# FPGA_DENDY_SE.net
KiCad netlist of a schematic drawn in EAGLE
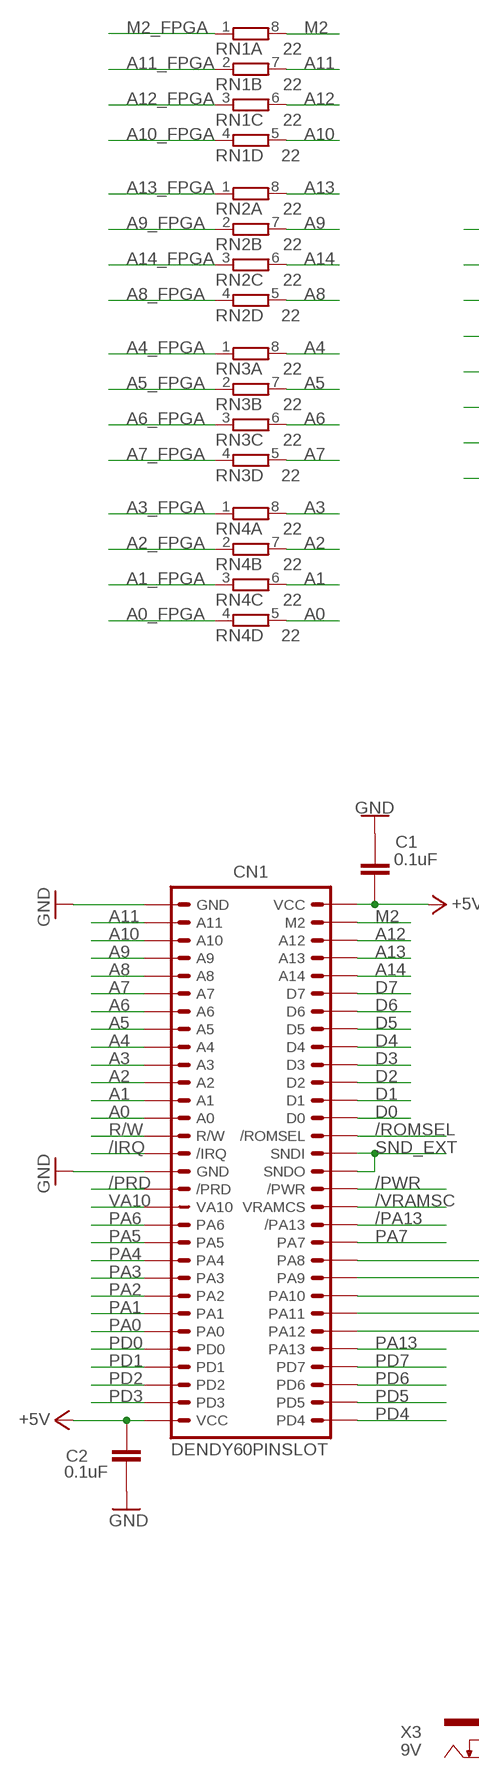
[diagram p0: schematic, sheet 1, part 1 of 2]
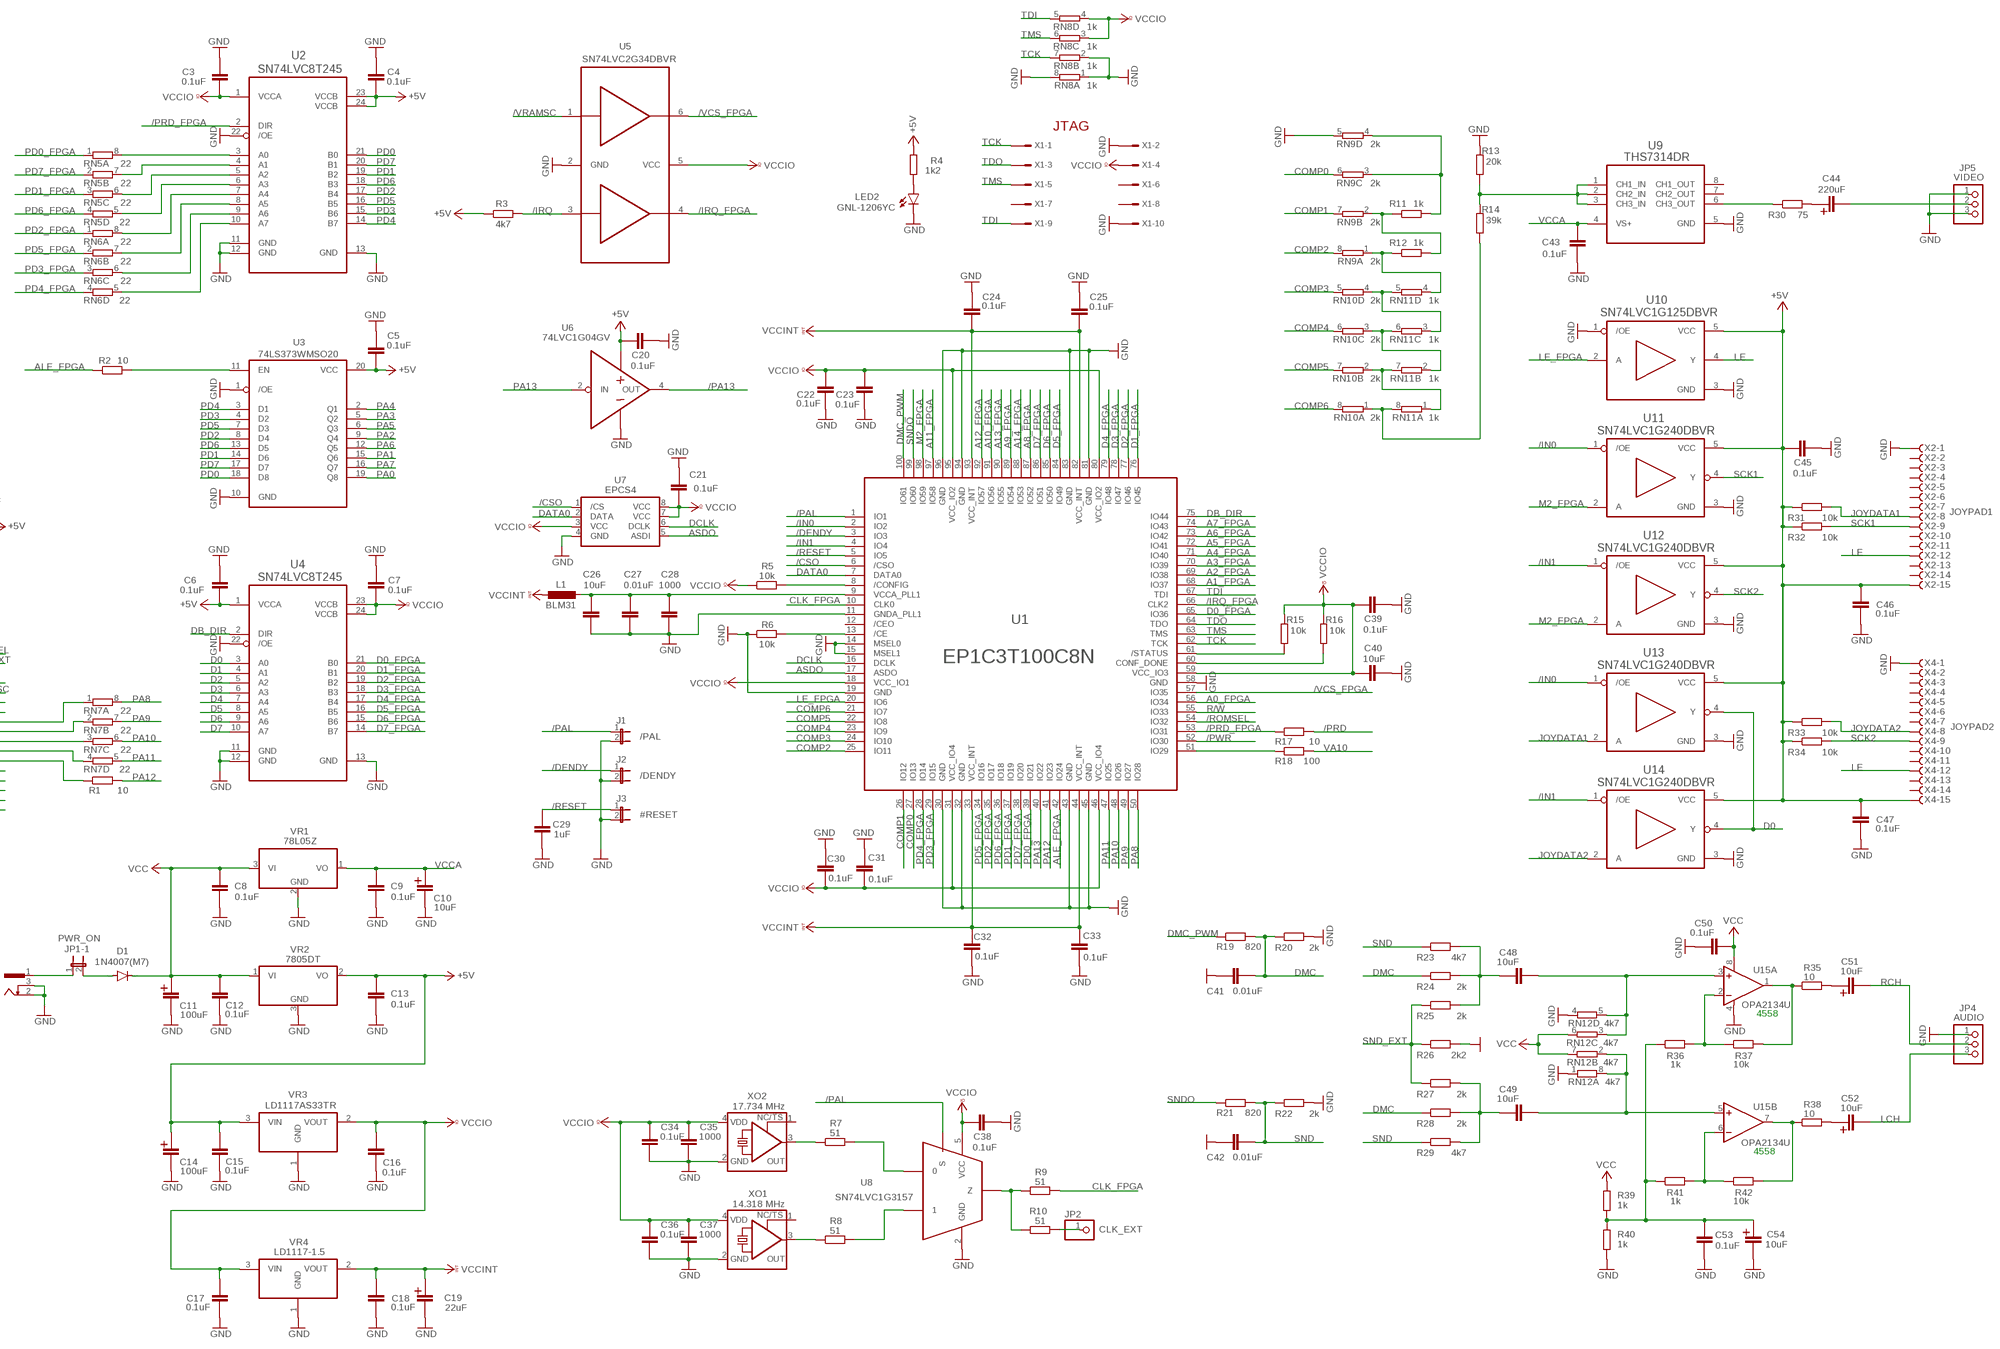
[diagram p1: schematic, sheet 1, part 2 of 2]

(export (version "E")
  (design (tool "Eeschema 10.0.6"))
  (components
    (comp (ref "C1")
      (value "0.1uF")
      (footprint "eagle-import:C0805")
      (libsource (lib "eagle-import") (part "C-EUC0805"))
    )
    (comp (ref "C2")
      (value "0.1uF")
      (footprint "eagle-import:C0805")
      (libsource (lib "eagle-import") (part "C-EUC0805"))
    )
    (comp (ref "C3")
      (value "0.1uF")
      (footprint "eagle-import:C0805")
      (libsource (lib "eagle-import") (part "C-EUC0805"))
    )
    (comp (ref "C4")
      (value "0.1uF")
      (footprint "eagle-import:C0805")
      (libsource (lib "eagle-import") (part "C-EUC0805"))
    )
    (comp (ref "C5")
      (value "0.1uF")
      (footprint "eagle-import:C0805")
      (libsource (lib "eagle-import") (part "C-EUC0805"))
    )
    (comp (ref "C6")
      (value "0.1uF")
      (footprint "eagle-import:C0603")
      (libsource (lib "eagle-import") (part "C-EUC0603"))
    )
    (comp (ref "C7")
      (value "0.1uF")
      (footprint "eagle-import:C0603")
      (libsource (lib "eagle-import") (part "C-EUC0603"))
    )
    (comp (ref "C8")
      (value "0.1uF")
      (footprint "eagle-import:C0805")
      (libsource (lib "eagle-import") (part "C-EUC0805"))
    )
    (comp (ref "C9")
      (value "0.1uF")
      (footprint "eagle-import:C0805")
      (libsource (lib "eagle-import") (part "C-EUC0805"))
    )
    (comp (ref "C10")
      (value "10uF")
      (footprint "eagle-import:153CLV-0505")
      (libsource (lib "eagle-import") (part "CPOL-EU153CLV-0505"))
    )
    (comp (ref "C11")
      (value "100uF")
      (footprint "eagle-import:153CLV-0505")
      (libsource (lib "eagle-import") (part "CPOL-EU153CLV-0505"))
    )
    (comp (ref "C12")
      (value "0.1uF")
      (footprint "eagle-import:C0805")
      (libsource (lib "eagle-import") (part "C-EUC0805"))
    )
    (comp (ref "C13")
      (value "0.1uF")
      (footprint "eagle-import:C0805")
      (libsource (lib "eagle-import") (part "C-EUC0805"))
    )
    (comp (ref "C14")
      (value "100uF")
      (footprint "eagle-import:153CLV-0505")
      (libsource (lib "eagle-import") (part "CPOL-EU153CLV-0505"))
    )
    (comp (ref "C15")
      (value "0.1uF")
      (footprint "eagle-import:C0805")
      (libsource (lib "eagle-import") (part "C-EUC0805"))
    )
    (comp (ref "C16")
      (value "0.1uF")
      (footprint "eagle-import:C0805")
      (libsource (lib "eagle-import") (part "C-EUC0805"))
    )
    (comp (ref "C17")
      (value "0.1uF")
      (footprint "eagle-import:C0805")
      (libsource (lib "eagle-import") (part "C-EUC0805"))
    )
    (comp (ref "C18")
      (value "0.1uF")
      (footprint "eagle-import:C0805")
      (libsource (lib "eagle-import") (part "C-EUC0805"))
    )
    (comp (ref "C19")
      (value "22uF")
      (footprint "eagle-import:153CLV-0505")
      (libsource (lib "eagle-import") (part "CPOL-EU153CLV-0505"))
    )
    (comp (ref "C20")
      (value "0.1uF")
      (footprint "eagle-import:C0603")
      (libsource (lib "eagle-import") (part "C-EUC0603"))
    )
    (comp (ref "C21")
      (value "0.1uF")
      (footprint "eagle-import:C0603")
      (libsource (lib "eagle-import") (part "C-EUC0603"))
    )
    (comp (ref "C22")
      (value "0.1uF")
      (footprint "eagle-import:C0603")
      (libsource (lib "eagle-import") (part "C-EUC0603"))
    )
    (comp (ref "C23")
      (value "0.1uF")
      (footprint "eagle-import:C0603")
      (libsource (lib "eagle-import") (part "C-EUC0603"))
    )
    (comp (ref "C24")
      (value "0.1uF")
      (footprint "eagle-import:C0603")
      (libsource (lib "eagle-import") (part "C-EUC0603"))
    )
    (comp (ref "C25")
      (value "0.1uF")
      (footprint "eagle-import:C0603")
      (libsource (lib "eagle-import") (part "C-EUC0603"))
    )
    (comp (ref "C26")
      (value "10uF")
      (footprint "eagle-import:C0603")
      (libsource (lib "eagle-import") (part "C-EUC0603"))
    )
    (comp (ref "C27")
      (value "0.01uF")
      (footprint "eagle-import:C0603")
      (libsource (lib "eagle-import") (part "C-EUC0603"))
    )
    (comp (ref "C28")
      (value "1000")
      (footprint "eagle-import:C0603")
      (libsource (lib "eagle-import") (part "C-EUC0603"))
    )
    (comp (ref "C29")
      (value "1uF")
      (footprint "eagle-import:C0603")
      (libsource (lib "eagle-import") (part "C-EUC0603"))
    )
    (comp (ref "C30")
      (value "0.1uF")
      (footprint "eagle-import:C0603")
      (libsource (lib "eagle-import") (part "C-EUC0603"))
    )
    (comp (ref "C31")
      (value "0.1uF")
      (footprint "eagle-import:C0603")
      (libsource (lib "eagle-import") (part "C-EUC0603"))
    )
    (comp (ref "C32")
      (value "0.1uF")
      (footprint "eagle-import:C0603")
      (libsource (lib "eagle-import") (part "C-EUC0603"))
    )
    (comp (ref "C33")
      (value "0.1uF")
      (footprint "eagle-import:C0603")
      (libsource (lib "eagle-import") (part "C-EUC0603"))
    )
    (comp (ref "C34")
      (value "0.1uF")
      (footprint "eagle-import:C0805")
      (libsource (lib "eagle-import") (part "C-EUC0805"))
    )
    (comp (ref "C35")
      (value "1000")
      (footprint "eagle-import:C0805")
      (libsource (lib "eagle-import") (part "C-EUC0805"))
    )
    (comp (ref "C36")
      (value "0.1uF")
      (footprint "eagle-import:C0805")
      (libsource (lib "eagle-import") (part "C-EUC0805"))
    )
    (comp (ref "C37")
      (value "1000")
      (footprint "eagle-import:C0805")
      (libsource (lib "eagle-import") (part "C-EUC0805"))
    )
    (comp (ref "C38")
      (value "0.1uF")
      (footprint "eagle-import:C0603")
      (libsource (lib "eagle-import") (part "C-EUC0603"))
    )
    (comp (ref "C39")
      (value "0.1uF")
      (footprint "eagle-import:C0603")
      (libsource (lib "eagle-import") (part "C-EUC0603"))
    )
    (comp (ref "C40")
      (value "10uF")
      (footprint "eagle-import:C0603")
      (libsource (lib "eagle-import") (part "C-EUC0603"))
    )
    (comp (ref "C41")
      (value "0.01uF")
      (footprint "eagle-import:C0805")
      (libsource (lib "eagle-import") (part "C-EUC0805"))
    )
    (comp (ref "C42")
      (value "0.01uF")
      (footprint "eagle-import:C0805")
      (libsource (lib "eagle-import") (part "C-EUC0805"))
    )
    (comp (ref "C43")
      (value "0.1uF")
      (footprint "eagle-import:C0603")
      (libsource (lib "eagle-import") (part "C-EUC0603"))
    )
    (comp (ref "C44")
      (value "220uF")
      (footprint "eagle-import:153CLV-0505")
      (libsource (lib "eagle-import") (part "CPOL-EU153CLV-0505"))
    )
    (comp (ref "C45")
      (value "0.1uF")
      (footprint "eagle-import:C0603")
      (libsource (lib "eagle-import") (part "C-EUC0603"))
    )
    (comp (ref "C46")
      (value "0.1uF")
      (footprint "eagle-import:C0805")
      (libsource (lib "eagle-import") (part "C-EUC0805"))
    )
    (comp (ref "C47")
      (value "0.1uF")
      (footprint "eagle-import:C0805")
      (libsource (lib "eagle-import") (part "C-EUC0805"))
    )
    (comp (ref "C48")
      (value "10uF")
      (footprint "eagle-import:C0805")
      (libsource (lib "eagle-import") (part "C-EUC0805"))
    )
    (comp (ref "C49")
      (value "10uF")
      (footprint "eagle-import:C0805")
      (libsource (lib "eagle-import") (part "C-EUC0805"))
    )
    (comp (ref "C50")
      (value "0.1uF")
      (footprint "eagle-import:C0805")
      (libsource (lib "eagle-import") (part "C-EUC0805"))
    )
    (comp (ref "C51")
      (value "10uF")
      (footprint "eagle-import:153CLV-0505")
      (libsource (lib "eagle-import") (part "CPOL-EU153CLV-0505"))
    )
    (comp (ref "C52")
      (value "10uF")
      (footprint "eagle-import:153CLV-0505")
      (libsource (lib "eagle-import") (part "CPOL-EU153CLV-0505"))
    )
    (comp (ref "C53")
      (value "0.1uF")
      (footprint "eagle-import:C0805")
      (libsource (lib "eagle-import") (part "C-EUC0805"))
    )
    (comp (ref "C54")
      (value "10uF")
      (footprint "eagle-import:153CLV-0505")
      (libsource (lib "eagle-import") (part "CPOL-EU153CLV-0505"))
    )
    (comp (ref "CN1")
      (value "DENDY60PINSLOT")
      (footprint "eagle-import:60PINDENDY")
      (libsource (lib "eagle-import") (part "DENDY60PINSLOT"))
    )
    (comp (ref "D1")
      (value "1N4007(M7)")
      (footprint "eagle-import:DO-214AC")
      (libsource (lib "eagle-import") (part "DIODE-DO-214AC"))
    )
    (comp (ref "J1")
      (value "/PAL")
      (footprint "eagle-import:JP1")
      (libsource (lib "eagle-import") (part "JP1E"))
    )
    (comp (ref "J2")
      (value "/DENDY")
      (footprint "eagle-import:JP1")
      (libsource (lib "eagle-import") (part "JP1E"))
    )
    (comp (ref "J3")
      (value "#RESET")
      (footprint "eagle-import:JP1")
      (libsource (lib "eagle-import") (part "JP1E"))
    )
    (comp (ref "JP1")
      (value "PWR_ON")
      (footprint "eagle-import:JP4Q")
      (libsource (lib "eagle-import") (part "JP4QE"))
    )
    (comp (ref "JP2")
      (value "CLK_EXT")
      (footprint "eagle-import:1X01")
      (libsource (lib "eagle-import") (part "PINHD-1X1"))
    )
    (comp (ref "JP4")
      (value "AUDIO")
      (footprint "eagle-import:1X03")
      (libsource (lib "eagle-import") (part "PINHD-1X3"))
    )
    (comp (ref "JP5")
      (value "VIDEO")
      (footprint "eagle-import:1X03")
      (libsource (lib "eagle-import") (part "PINHD-1X3"))
    )
    (comp (ref "L1")
      (value "BLM31")
      (footprint "eagle-import:L0201")
      (libsource (lib "eagle-import") (part "L-EUL0201"))
    )
    (comp (ref "LED2")
      (value "GNL-1206YC")
      (footprint "eagle-import:SML1206")
      (libsource (lib "eagle-import") (part "LEDSML1206"))
    )
    (comp (ref "R1")
      (value "10")
      (footprint "eagle-import:R0805")
      (libsource (lib "eagle-import") (part "R-EU_R0805"))
    )
    (comp (ref "R2")
      (value "10")
      (footprint "eagle-import:R0805")
      (libsource (lib "eagle-import") (part "R-EU_R0805"))
    )
    (comp (ref "R3")
      (value "4k7")
      (footprint "eagle-import:R0805")
      (libsource (lib "eagle-import") (part "R-EU_R0805"))
    )
    (comp (ref "R4")
      (value "1k2")
      (footprint "eagle-import:R0805")
      (libsource (lib "eagle-import") (part "R-EU_R0805"))
    )
    (comp (ref "R5")
      (value "10k")
      (footprint "eagle-import:R0805")
      (libsource (lib "eagle-import") (part "R-EU_R0805"))
    )
    (comp (ref "R6")
      (value "10k")
      (footprint "eagle-import:R0805")
      (libsource (lib "eagle-import") (part "R-EU_R0805"))
    )
    (comp (ref "R7")
      (value "51")
      (footprint "eagle-import:R0805")
      (libsource (lib "eagle-import") (part "R-EU_R0805"))
    )
    (comp (ref "R8")
      (value "51")
      (footprint "eagle-import:R0805")
      (libsource (lib "eagle-import") (part "R-EU_R0805"))
    )
    (comp (ref "R9")
      (value "51")
      (footprint "eagle-import:R0805")
      (libsource (lib "eagle-import") (part "R-EU_R0805"))
    )
    (comp (ref "R10")
      (value "51")
      (footprint "eagle-import:R0805")
      (libsource (lib "eagle-import") (part "R-EU_R0805"))
    )
    (comp (ref "R11")
      (value "1k")
      (footprint "eagle-import:R0805")
      (libsource (lib "eagle-import") (part "R-EU_R0805"))
    )
    (comp (ref "R12")
      (value "1k")
      (footprint "eagle-import:R0805")
      (libsource (lib "eagle-import") (part "R-EU_R0805"))
    )
    (comp (ref "R13")
      (value "20k")
      (footprint "eagle-import:R0805")
      (libsource (lib "eagle-import") (part "R-EU_R0805"))
    )
    (comp (ref "R14")
      (value "39k")
      (footprint "eagle-import:R0805")
      (libsource (lib "eagle-import") (part "R-EU_R0805"))
    )
    (comp (ref "R15")
      (value "10k")
      (footprint "eagle-import:R0805")
      (libsource (lib "eagle-import") (part "R-EU_R0805"))
    )
    (comp (ref "R16")
      (value "10k")
      (footprint "eagle-import:R0805")
      (libsource (lib "eagle-import") (part "R-EU_R0805"))
    )
    (comp (ref "R17")
      (value "10")
      (footprint "eagle-import:R0805")
      (libsource (lib "eagle-import") (part "R-EU_R0805"))
    )
    (comp (ref "R18")
      (value "100")
      (footprint "eagle-import:R0805")
      (libsource (lib "eagle-import") (part "R-EU_R0805"))
    )
    (comp (ref "R19")
      (value "820")
      (footprint "eagle-import:R0805")
      (libsource (lib "eagle-import") (part "R-EU_R0805"))
    )
    (comp (ref "R20")
      (value "2k")
      (footprint "eagle-import:R0805")
      (libsource (lib "eagle-import") (part "R-EU_R0805"))
    )
    (comp (ref "R21")
      (value "820")
      (footprint "eagle-import:R0805")
      (libsource (lib "eagle-import") (part "R-EU_R0805"))
    )
    (comp (ref "R22")
      (value "2k")
      (footprint "eagle-import:R0805")
      (libsource (lib "eagle-import") (part "R-EU_R0805"))
    )
    (comp (ref "R23")
      (value "4k7")
      (footprint "eagle-import:R0805")
      (libsource (lib "eagle-import") (part "R-EU_R0805"))
    )
    (comp (ref "R24")
      (value "2k")
      (footprint "eagle-import:R0805")
      (libsource (lib "eagle-import") (part "R-EU_R0805"))
    )
    (comp (ref "R25")
      (value "2k")
      (footprint "eagle-import:R0805")
      (libsource (lib "eagle-import") (part "R-EU_R0805"))
    )
    (comp (ref "R26")
      (value "2k2")
      (footprint "eagle-import:R0805")
      (libsource (lib "eagle-import") (part "R-EU_R0805"))
    )
    (comp (ref "R27")
      (value "2k")
      (footprint "eagle-import:R0805")
      (libsource (lib "eagle-import") (part "R-EU_R0805"))
    )
    (comp (ref "R28")
      (value "2k")
      (footprint "eagle-import:R0805")
      (libsource (lib "eagle-import") (part "R-EU_R0805"))
    )
    (comp (ref "R29")
      (value "4k7")
      (footprint "eagle-import:R0805")
      (libsource (lib "eagle-import") (part "R-EU_R0805"))
    )
    (comp (ref "R30")
      (value "75")
      (footprint "eagle-import:R0805")
      (libsource (lib "eagle-import") (part "R-EU_R0805"))
    )
    (comp (ref "R31")
      (value "10k")
      (footprint "eagle-import:R0805")
      (libsource (lib "eagle-import") (part "R-EU_R0805"))
    )
    (comp (ref "R32")
      (value "10k")
      (footprint "eagle-import:R0805")
      (libsource (lib "eagle-import") (part "R-EU_R0805"))
    )
    (comp (ref "R33")
      (value "10k")
      (footprint "eagle-import:R0805")
      (libsource (lib "eagle-import") (part "R-EU_R0805"))
    )
    (comp (ref "R34")
      (value "10k")
      (footprint "eagle-import:R0805")
      (libsource (lib "eagle-import") (part "R-EU_R0805"))
    )
    (comp (ref "R35")
      (value "10")
      (footprint "eagle-import:R0805")
      (libsource (lib "eagle-import") (part "R-EU_R0805"))
    )
    (comp (ref "R36")
      (value "1k")
      (footprint "eagle-import:R0805")
      (libsource (lib "eagle-import") (part "R-EU_R0805"))
    )
    (comp (ref "R37")
      (value "10k")
      (footprint "eagle-import:R0805")
      (libsource (lib "eagle-import") (part "R-EU_R0805"))
    )
    (comp (ref "R38")
      (value "10")
      (footprint "eagle-import:R0805")
      (libsource (lib "eagle-import") (part "R-EU_R0805"))
    )
    (comp (ref "R39")
      (value "1k")
      (footprint "eagle-import:R0805")
      (libsource (lib "eagle-import") (part "R-EU_R0805"))
    )
    (comp (ref "R40")
      (value "1k")
      (footprint "eagle-import:R0805")
      (libsource (lib "eagle-import") (part "R-EU_R0805"))
    )
    (comp (ref "R41")
      (value "1k")
      (footprint "eagle-import:R0805")
      (libsource (lib "eagle-import") (part "R-EU_R0805"))
    )
    (comp (ref "R42")
      (value "10k")
      (footprint "eagle-import:R0805")
      (libsource (lib "eagle-import") (part "R-EU_R0805"))
    )
    (comp (ref "RN1")
      (value "22")
      (footprint "eagle-import:0603-ARC")
      (libsource (lib "eagle-import") (part "4R-N0603-ARC"))
    )
    (comp (ref "RN2")
      (value "22")
      (footprint "eagle-import:0603-ARC")
      (libsource (lib "eagle-import") (part "4R-N0603-ARC"))
    )
    (comp (ref "RN3")
      (value "22")
      (footprint "eagle-import:0603-ARC")
      (libsource (lib "eagle-import") (part "4R-N0603-ARC"))
    )
    (comp (ref "RN4")
      (value "22")
      (footprint "eagle-import:0603-ARC")
      (libsource (lib "eagle-import") (part "4R-N0603-ARC"))
    )
    (comp (ref "RN5")
      (value "22")
      (footprint "eagle-import:0603-ARC")
      (libsource (lib "eagle-import") (part "4R-N0603-ARC"))
    )
    (comp (ref "RN6")
      (value "22")
      (footprint "eagle-import:0603-ARC")
      (libsource (lib "eagle-import") (part "4R-N0603-ARC"))
    )
    (comp (ref "RN7")
      (value "22")
      (footprint "eagle-import:0603-ARC")
      (libsource (lib "eagle-import") (part "4R-N0603-ARC"))
    )
    (comp (ref "RN8")
      (value "1k")
      (footprint "eagle-import:0603-ARC")
      (libsource (lib "eagle-import") (part "4R-N0603-ARC"))
    )
    (comp (ref "RN9")
      (value "2k")
      (footprint "eagle-import:0603-ARC")
      (libsource (lib "eagle-import") (part "4R-N0603-ARC"))
    )
    (comp (ref "RN10")
      (value "2k")
      (footprint "eagle-import:0603-ARC")
      (libsource (lib "eagle-import") (part "4R-N0603-ARC"))
    )
    (comp (ref "RN11")
      (value "1k")
      (footprint "eagle-import:0603-ARC")
      (libsource (lib "eagle-import") (part "4R-N0603-ARC"))
    )
    (comp (ref "RN12")
      (value "4k7")
      (footprint "eagle-import:0603-ARC")
      (libsource (lib "eagle-import") (part "4R-N0603-ARC"))
    )
    (comp (ref "U1")
      (value "EP1C3T100C8N")
      (footprint "eagle-import:QFP50P1600X1600X120-100N")
      (libsource (lib "eagle-import") (part "EP1C3T100C8N"))
    )
    (comp (ref "U2")
      (value "SN74LVC8T245")
      (footprint "eagle-import:SOP65P640X110-24N")
      (libsource (lib "eagle-import") (part "SN74LVC8T245"))
    )
    (comp (ref "U3")
      (value "74LS373WMSO20")
      (footprint "eagle-import:SO20W")
      (libsource (lib "eagle-import") (part "74LS373WMSO20"))
    )
    (comp (ref "U4")
      (value "SN74LVC8T245")
      (footprint "eagle-import:SOP65P640X110-24N")
      (libsource (lib "eagle-import") (part "SN74LVC8T245"))
    )
    (comp (ref "U5")
      (value "SN74LVC2G34DBVR")
      (footprint "eagle-import:SOT-23-6")
      (libsource (lib "eagle-import") (part "SN74LVC2G34DBVR"))
    )
    (comp (ref "U6")
      (value "74LVC1G04GV")
      (footprint "eagle-import:SOT95P275X110-5N")
      (libsource (lib "eagle-import") (part "74LVC1G04GV"))
    )
    (comp (ref "U7")
      (value "EPCS4")
      (footprint "eagle-import:SO08")
      (libsource (lib "eagle-import") (part "EPCS4"))
    )
    (comp (ref "U8")
      (value "SN74LVC1G3157")
      (footprint "eagle-import:SOT-23-6")
      (libsource (lib "eagle-import") (part "SN74LVC1G3157"))
    )
    (comp (ref "U9")
      (value "THS7314DR")
      (footprint "eagle-import:SO8")
      (libsource (lib "eagle-import") (part "THS7314"))
    )
    (comp (ref "U10")
      (value "SN74LVC1G125DBVR")
      (footprint "eagle-import:SOT95P280X145-5N")
      (libsource (lib "eagle-import") (part "SN74LVC1G125DBVR"))
    )
    (comp (ref "U11")
      (value "SN74LVC1G240DBVR")
      (footprint "eagle-import:SOT95P280X145-5N")
      (libsource (lib "eagle-import") (part "SN74LVC1G240DBVR"))
    )
    (comp (ref "U12")
      (value "SN74LVC1G240DBVR")
      (footprint "eagle-import:SOT95P280X145-5N")
      (libsource (lib "eagle-import") (part "SN74LVC1G240DBVR"))
    )
    (comp (ref "U13")
      (value "SN74LVC1G240DBVR")
      (footprint "eagle-import:SOT95P280X145-5N")
      (libsource (lib "eagle-import") (part "SN74LVC1G240DBVR"))
    )
    (comp (ref "U14")
      (value "SN74LVC1G240DBVR")
      (footprint "eagle-import:SOT95P280X145-5N")
      (libsource (lib "eagle-import") (part "SN74LVC1G240DBVR"))
    )
    (comp (ref "U15")
      (value "OPA2134U")
      (footprint "eagle-import:SO08")
      (fields (field (name "MF") "TEXAS INSTRUMENTS") (field (name "MPN") "OPA2134UA"))
      (libsource (lib "eagle-import") (part "OPA2134U"))
    )
    (comp (ref "VR1")
      (value "78L05Z")
      (footprint "eagle-import:TO92")
      (libsource (lib "eagle-import") (part "78ZL05"))
    )
    (comp (ref "VR2")
      (value "7805DT")
      (footprint "eagle-import:TO252")
      (libsource (lib "eagle-import") (part "linear stab_78DT05"))
    )
    (comp (ref "VR3")
      (value "LD1117AS33TR")
      (footprint "eagle-import:SOT230P700X180-4N")
      (libsource (lib "eagle-import") (part "LD1117AS33TR"))
    )
    (comp (ref "VR4")
      (value "LD1117-1.5")
      (footprint "eagle-import:SOT-223-3")
      (libsource (lib "eagle-import") (part "LD1117-1.5"))
    )
    (comp (ref "X1")
      (value "057-010-1")
      (footprint "eagle-import:057-010-1")
      (libsource (lib "eagle-import") (part "057-010-1"))
    )
    (comp (ref "X2")
      (value "JOYPAD1")
      (footprint "eagle-import:F15HP")
      (libsource (lib "eagle-import") (part "F15HPS"))
    )
    (comp (ref "X3")
      (value "9V")
      (footprint "eagle-import:733980-62")
      (libsource (lib "eagle-import") (part "73398?0-62"))
    )
    (comp (ref "X4")
      (value "JOYPAD2")
      (footprint "eagle-import:F15HP")
      (libsource (lib "eagle-import") (part "F15HPS"))
    )
    (comp (ref "XO1")
      (value "14.318 MHz")
      (footprint "eagle-import:7.0X5.08_KXO-(V)97")
      (libsource (lib "eagle-import") (part "KXO-PXO/XO-V97"))
    )
    (comp (ref "XO2")
      (value "17.734 MHz")
      (footprint "eagle-import:2.5X2.0_KXO-V95")
      (libsource (lib "eagle-import") (part "KXO-PXO/XO-V95"))
    )
  )
  (nets
    (net (code "1") (name "+5V") (class "Default")
      (node (ref "C1") (pin "2") (pinfunction "2_2") (pintype "passive"))
      (node (ref "C13") (pin "1") (pinfunction "1_1") (pintype "passive"))
      (node (ref "C14") (pin "+") (pinfunction "+_+") (pintype "passive"))
      (node (ref "C15") (pin "1") (pinfunction "1_1") (pintype "passive"))
      (node (ref "C2") (pin "1") (pinfunction "1_1") (pintype "passive"))
      (node (ref "C20") (pin "2") (pinfunction "2_2") (pintype "passive"))
      (node (ref "C4") (pin "2") (pinfunction "2_2") (pintype "passive"))
      (node (ref "C45") (pin "2") (pinfunction "2_2") (pintype "passive"))
      (node (ref "C46") (pin "1") (pinfunction "1_1") (pintype "passive"))
      (node (ref "C47") (pin "1") (pinfunction "1_1") (pintype "passive"))
      (node (ref "C5") (pin "2") (pinfunction "2_2") (pintype "passive"))
      (node (ref "C6") (pin "1") (pinfunction "1_1") (pintype "passive"))
      (node (ref "CN1") (pin "A30") (pinfunction "VCC_A30") (pintype "power_in"))
      (node (ref "CN1") (pin "B1") (pinfunction "VCC_B1") (pintype "power_in"))
      (node (ref "R3") (pin "1") (pinfunction "1_1") (pintype "passive"))
      (node (ref "R31") (pin "1") (pinfunction "1_1") (pintype "passive"))
      (node (ref "R32") (pin "1") (pinfunction "1_1") (pintype "passive"))
      (node (ref "R33") (pin "1") (pinfunction "1_1") (pintype "passive"))
      (node (ref "R34") (pin "1") (pinfunction "1_1") (pintype "passive"))
      (node (ref "R4") (pin "2") (pinfunction "2_2") (pintype "passive"))
      (node (ref "U10") (pin "5") (pinfunction "VCC_5") (pintype "power_in"))
      (node (ref "U11") (pin "5") (pinfunction "VCC_5") (pintype "power_in"))
      (node (ref "U12") (pin "5") (pinfunction "VCC_5") (pintype "power_in"))
      (node (ref "U13") (pin "5") (pinfunction "VCC_5") (pintype "power_in"))
      (node (ref "U14") (pin "5") (pinfunction "VCC_5") (pintype "power_in"))
      (node (ref "U2") (pin "23") (pinfunction "VCCB_23") (pintype "power_in"))
      (node (ref "U2") (pin "24") (pinfunction "VCCB_24") (pintype "power_in"))
      (node (ref "U3") (pin "20") (pinfunction "VCC_20") (pintype "power_in"))
      (node (ref "U4") (pin "1") (pinfunction "VCCA_1") (pintype "power_in"))
      (node (ref "U6") (pin "5") (pinfunction "VCC_5") (pintype "power_in"))
      (node (ref "VR2") (pin "2") (pinfunction "VO_2") (pintype "passive"))
      (node (ref "VR3") (pin "3") (pinfunction "VIN_3") (pintype "power_in"))
      (node (ref "X2") (pin "15") (pinfunction "F_15") (pintype "passive"))
      (node (ref "X4") (pin "15") (pinfunction "F_15") (pintype "passive"))
    )
    (net (code "2") (name "/A0") (class "Default")
      (node (ref "CN1") (pin "A13") (pinfunction "A0_A13") (pintype "input"))
      (node (ref "RN4") (pin "5") (pinfunction "2_5") (pintype "passive"))
    )
    (net (code "3") (name "/A0_FPGA") (class "Default")
      (node (ref "RN4") (pin "4") (pinfunction "1_4") (pintype "passive"))
      (node (ref "U1") (pin "56") (pinfunction "IO34_56") (pintype "bidirectional"))
    )
    (net (code "4") (name "/A1") (class "Default")
      (node (ref "CN1") (pin "A12") (pinfunction "A1_A12") (pintype "bidirectional"))
      (node (ref "RN4") (pin "6") (pinfunction "2_6") (pintype "passive"))
    )
    (net (code "5") (name "/A1_FPGA") (class "Default")
      (node (ref "RN4") (pin "3") (pinfunction "1_3") (pintype "passive"))
      (node (ref "U1") (pin "68") (pinfunction "IO37_68") (pintype "bidirectional"))
    )
    (net (code "6") (name "/A2") (class "Default")
      (node (ref "CN1") (pin "A11") (pinfunction "A2_A11") (pintype "input"))
      (node (ref "RN4") (pin "7") (pinfunction "2_7") (pintype "passive"))
    )
    (net (code "7") (name "/A2_FPGA") (class "Default")
      (node (ref "RN4") (pin "2") (pinfunction "1_2") (pintype "passive"))
      (node (ref "U1") (pin "69") (pinfunction "IO38_69") (pintype "bidirectional"))
    )
    (net (code "8") (name "/A3") (class "Default")
      (node (ref "CN1") (pin "A10") (pinfunction "A3_A10") (pintype "input"))
      (node (ref "RN4") (pin "8") (pinfunction "2_8") (pintype "passive"))
    )
    (net (code "9") (name "/A3_FPGA") (class "Default")
      (node (ref "RN4") (pin "1") (pinfunction "1_1") (pintype "passive"))
      (node (ref "U1") (pin "70") (pinfunction "IO39_70") (pintype "bidirectional"))
    )
    (net (code "10") (name "/A4") (class "Default")
      (node (ref "CN1") (pin "A9") (pinfunction "A4_A9") (pintype "input"))
      (node (ref "RN3") (pin "8") (pinfunction "2_8") (pintype "passive"))
    )
    (net (code "11") (name "/A4_FPGA") (class "Default")
      (node (ref "RN3") (pin "1") (pinfunction "1_1") (pintype "passive"))
      (node (ref "U1") (pin "71") (pinfunction "IO40_71") (pintype "bidirectional"))
    )
    (net (code "12") (name "/A5") (class "Default")
      (node (ref "CN1") (pin "A8") (pinfunction "A5_A8") (pintype "input"))
      (node (ref "RN3") (pin "7") (pinfunction "2_7") (pintype "passive"))
    )
    (net (code "13") (name "/A5_FPGA") (class "Default")
      (node (ref "RN3") (pin "2") (pinfunction "1_2") (pintype "passive"))
      (node (ref "U1") (pin "72") (pinfunction "IO41_72") (pintype "bidirectional"))
    )
    (net (code "14") (name "/A6") (class "Default")
      (node (ref "CN1") (pin "A7") (pinfunction "A6_A7") (pintype "input"))
      (node (ref "RN3") (pin "6") (pinfunction "2_6") (pintype "passive"))
    )
    (net (code "15") (name "/A6_FPGA") (class "Default")
      (node (ref "RN3") (pin "3") (pinfunction "1_3") (pintype "passive"))
      (node (ref "U1") (pin "73") (pinfunction "IO42_73") (pintype "bidirectional"))
    )
    (net (code "16") (name "/A7") (class "Default")
      (node (ref "CN1") (pin "A6") (pinfunction "A7_A6") (pintype "input"))
      (node (ref "RN3") (pin "5") (pinfunction "2_5") (pintype "passive"))
    )
    (net (code "17") (name "/A7_FPGA") (class "Default")
      (node (ref "RN3") (pin "4") (pinfunction "1_4") (pintype "passive"))
      (node (ref "U1") (pin "74") (pinfunction "IO43_74") (pintype "bidirectional"))
    )
    (net (code "18") (name "/A8") (class "Default")
      (node (ref "CN1") (pin "A5") (pinfunction "A8_A5") (pintype "input"))
      (node (ref "RN2") (pin "5") (pinfunction "2_5") (pintype "passive"))
    )
    (net (code "19") (name "/A8_FPGA") (class "Default")
      (node (ref "RN2") (pin "4") (pinfunction "1_4") (pintype "passive"))
      (node (ref "U1") (pin "87") (pinfunction "IO52_87") (pintype "bidirectional"))
    )
    (net (code "20") (name "/A9") (class "Default")
      (node (ref "CN1") (pin "A4") (pinfunction "A9_A4") (pintype "input"))
      (node (ref "RN2") (pin "7") (pinfunction "2_7") (pintype "passive"))
    )
    (net (code "21") (name "/A9_FPGA") (class "Default")
      (node (ref "RN2") (pin "2") (pinfunction "1_2") (pintype "passive"))
      (node (ref "U1") (pin "89") (pinfunction "IO54_89") (pintype "bidirectional"))
    )
    (net (code "22") (name "/A10") (class "Default")
      (node (ref "CN1") (pin "A3") (pinfunction "A10_A3") (pintype "input"))
      (node (ref "RN1") (pin "5") (pinfunction "2_5") (pintype "passive"))
    )
    (net (code "23") (name "/A10_FPGA") (class "Default")
      (node (ref "RN1") (pin "4") (pinfunction "1_4") (pintype "passive"))
      (node (ref "U1") (pin "91") (pinfunction "IO56_91") (pintype "bidirectional"))
    )
    (net (code "24") (name "/A11") (class "Default")
      (node (ref "CN1") (pin "A2") (pinfunction "A11_A2") (pintype "input"))
      (node (ref "RN1") (pin "7") (pinfunction "2_7") (pintype "passive"))
    )
    (net (code "25") (name "/A11_FPGA") (class "Default")
      (node (ref "RN1") (pin "2") (pinfunction "1_2") (pintype "passive"))
      (node (ref "U1") (pin "97") (pinfunction "IO58_97") (pintype "bidirectional"))
    )
    (net (code "26") (name "/A12") (class "Default")
      (node (ref "CN1") (pin "B3") (pinfunction "A12_B3") (pintype "input"))
      (node (ref "RN1") (pin "6") (pinfunction "2_6") (pintype "passive"))
    )
    (net (code "27") (name "/A12_FPGA") (class "Default")
      (node (ref "RN1") (pin "3") (pinfunction "1_3") (pintype "passive"))
      (node (ref "U1") (pin "92") (pinfunction "IO57_92") (pintype "bidirectional"))
    )
    (net (code "28") (name "/A13") (class "Default")
      (node (ref "CN1") (pin "B4") (pinfunction "A13_B4") (pintype "input"))
      (node (ref "RN2") (pin "8") (pinfunction "2_8") (pintype "passive"))
    )
    (net (code "29") (name "/A13_FPGA") (class "Default")
      (node (ref "RN2") (pin "1") (pinfunction "1_1") (pintype "passive"))
      (node (ref "U1") (pin "90") (pinfunction "IO55_90") (pintype "bidirectional"))
    )
    (net (code "30") (name "/A14") (class "Default")
      (node (ref "CN1") (pin "B5") (pinfunction "A14_B5") (pintype "input"))
      (node (ref "RN2") (pin "6") (pinfunction "2_6") (pintype "passive"))
    )
    (net (code "31") (name "/A14_FPGA") (class "Default")
      (node (ref "RN2") (pin "3") (pinfunction "1_3") (pintype "passive"))
      (node (ref "U1") (pin "88") (pinfunction "IO53_88") (pintype "bidirectional"))
    )
    (net (code "32") (name "/ALE_FPGA") (class "Default")
      (node (ref "R2") (pin "1") (pinfunction "1_1") (pintype "passive"))
      (node (ref "U1") (pin "42") (pinfunction "IO24_42") (pintype "bidirectional"))
    )
    (net (code "33") (name "/ASDO") (class "Default")
      (node (ref "U1") (pin "17") (pinfunction "ASDO_17") (pintype "output"))
      (node (ref "U7") (pin "5") (pinfunction "ASDI_5") (pintype "input"))
    )
    (net (code "34") (name "/CLK_FPGA") (class "Default")
      (node (ref "R9") (pin "2") (pinfunction "2_2") (pintype "passive"))
      (node (ref "U1") (pin "10") (pinfunction "CLK0_10") (pintype "input"))
    )
    (net (code "35") (name "/COMP0") (class "Default")
      (node (ref "RN9") (pin "6") (pinfunction "2_6") (pintype "passive"))
      (node (ref "U1") (pin "27") (pinfunction "IO13_27") (pintype "bidirectional"))
    )
    (net (code "36") (name "/COMP1") (class "Default")
      (node (ref "RN9") (pin "7") (pinfunction "2_7") (pintype "passive"))
      (node (ref "U1") (pin "26") (pinfunction "IO12_26") (pintype "bidirectional"))
    )
    (net (code "37") (name "/COMP2") (class "Default")
      (node (ref "RN9") (pin "8") (pinfunction "2_8") (pintype "passive"))
      (node (ref "U1") (pin "25") (pinfunction "IO11_25") (pintype "bidirectional"))
    )
    (net (code "38") (name "/COMP3") (class "Default")
      (node (ref "RN10") (pin "5") (pinfunction "2_5") (pintype "passive"))
      (node (ref "U1") (pin "24") (pinfunction "IO10_24") (pintype "bidirectional"))
    )
    (net (code "39") (name "/COMP4") (class "Default")
      (node (ref "RN10") (pin "6") (pinfunction "2_6") (pintype "passive"))
      (node (ref "U1") (pin "23") (pinfunction "IO9_23") (pintype "bidirectional"))
    )
    (net (code "40") (name "/COMP5") (class "Default")
      (node (ref "RN10") (pin "7") (pinfunction "2_7") (pintype "passive"))
      (node (ref "U1") (pin "22") (pinfunction "IO8_22") (pintype "bidirectional"))
    )
    (net (code "41") (name "/COMP6") (class "Default")
      (node (ref "RN10") (pin "8") (pinfunction "2_8") (pintype "passive"))
      (node (ref "U1") (pin "21") (pinfunction "IO7_21") (pintype "bidirectional"))
    )
    (net (code "42") (name "/D0") (class "Default")
      (node (ref "CN1") (pin "B13") (pinfunction "D0_B13") (pintype "bidirectional"))
      (node (ref "U13") (pin "4") (pinfunction "Y_4") (pintype "tri_state"))
      (node (ref "U14") (pin "4") (pinfunction "Y_4") (pintype "tri_state"))
      (node (ref "U4") (pin "3") (pinfunction "A0_3") (pintype "bidirectional"))
    )
    (net (code "43") (name "/D0_FPGA") (class "Default")
      (node (ref "U1") (pin "65") (pinfunction "IO36_65") (pintype "bidirectional"))
      (node (ref "U4") (pin "21") (pinfunction "B0_21") (pintype "bidirectional"))
    )
    (net (code "44") (name "/D1") (class "Default")
      (node (ref "CN1") (pin "B12") (pinfunction "D1_B12") (pintype "bidirectional"))
      (node (ref "U4") (pin "4") (pinfunction "A1_4") (pintype "bidirectional"))
    )
    (net (code "45") (name "/D1_FPGA") (class "Default")
      (node (ref "U1") (pin "76") (pinfunction "IO45_76") (pintype "bidirectional"))
      (node (ref "U4") (pin "20") (pinfunction "B1_20") (pintype "bidirectional"))
    )
    (net (code "46") (name "/D2") (class "Default")
      (node (ref "CN1") (pin "B11") (pinfunction "D2_B11") (pintype "bidirectional"))
      (node (ref "U4") (pin "5") (pinfunction "A2_5") (pintype "bidirectional"))
    )
    (net (code "47") (name "/D2_FPGA") (class "Default")
      (node (ref "U1") (pin "77") (pinfunction "IO46_77") (pintype "bidirectional"))
      (node (ref "U4") (pin "19") (pinfunction "B2_19") (pintype "bidirectional"))
    )
    (net (code "48") (name "/D3") (class "Default")
      (node (ref "CN1") (pin "B10") (pinfunction "D3_B10") (pintype "bidirectional"))
      (node (ref "U4") (pin "6") (pinfunction "A3_6") (pintype "bidirectional"))
    )
    (net (code "49") (name "/D3_FPGA") (class "Default")
      (node (ref "U1") (pin "78") (pinfunction "IO47_78") (pintype "bidirectional"))
      (node (ref "U4") (pin "18") (pinfunction "B3_18") (pintype "bidirectional"))
    )
    (net (code "50") (name "/D4") (class "Default")
      (node (ref "CN1") (pin "B9") (pinfunction "D4_B9") (pintype "bidirectional"))
      (node (ref "U4") (pin "7") (pinfunction "A4_7") (pintype "bidirectional"))
    )
    (net (code "51") (name "/D4_FPGA") (class "Default")
      (node (ref "U1") (pin "79") (pinfunction "IO48_79") (pintype "bidirectional"))
      (node (ref "U4") (pin "17") (pinfunction "B4_17") (pintype "bidirectional"))
    )
    (net (code "52") (name "/D5") (class "Default")
      (node (ref "CN1") (pin "B8") (pinfunction "D5_B8") (pintype "bidirectional"))
      (node (ref "U4") (pin "8") (pinfunction "A5_8") (pintype "bidirectional"))
    )
    (net (code "53") (name "/D5_FPGA") (class "Default")
      (node (ref "U1") (pin "84") (pinfunction "IO49_84") (pintype "bidirectional"))
      (node (ref "U4") (pin "16") (pinfunction "B5_16") (pintype "bidirectional"))
    )
    (net (code "54") (name "/D6") (class "Default")
      (node (ref "CN1") (pin "B7") (pinfunction "D6_B7") (pintype "bidirectional"))
      (node (ref "U4") (pin "9") (pinfunction "A6_9") (pintype "bidirectional"))
    )
    (net (code "55") (name "/D6_FPGA") (class "Default")
      (node (ref "U1") (pin "85") (pinfunction "IO50_85") (pintype "bidirectional"))
      (node (ref "U4") (pin "15") (pinfunction "B6_15") (pintype "bidirectional"))
    )
    (net (code "56") (name "/D7") (class "Default")
      (node (ref "CN1") (pin "B6") (pinfunction "D7_B6") (pintype "bidirectional"))
      (node (ref "U4") (pin "10") (pinfunction "A7_10") (pintype "bidirectional"))
    )
    (net (code "57") (name "/D7_FPGA") (class "Default")
      (node (ref "U1") (pin "86") (pinfunction "IO51_86") (pintype "bidirectional"))
      (node (ref "U4") (pin "14") (pinfunction "B7_14") (pintype "bidirectional"))
    )
    (net (code "58") (name "/DATA0") (class "Default")
      (node (ref "U1") (pin "7") (pinfunction "DATA0_7") (pintype "input"))
      (node (ref "U7") (pin "2") (pinfunction "DATA_2") (pintype "output"))
    )
    (net (code "59") (name "/DB_DIR") (class "Default")
      (node (ref "U1") (pin "75") (pinfunction "IO44_75") (pintype "bidirectional"))
      (node (ref "U4") (pin "2") (pinfunction "DIR_2") (pintype "input"))
    )
    (net (code "60") (name "/DCLK") (class "Default")
      (node (ref "U1") (pin "16") (pinfunction "DCLK_16") (pintype "bidirectional"))
      (node (ref "U7") (pin "6") (pinfunction "DCLK_6") (pintype "input"))
    )
    (net (code "61") (name "/DMC") (class "Default")
      (node (ref "C41") (pin "2") (pinfunction "2_2") (pintype "passive"))
      (node (ref "R19") (pin "2") (pinfunction "2_2") (pintype "passive"))
      (node (ref "R20") (pin "1") (pinfunction "1_1") (pintype "passive"))
      (node (ref "R24") (pin "1") (pinfunction "1_1") (pintype "passive"))
      (node (ref "R28") (pin "1") (pinfunction "1_1") (pintype "passive"))
    )
    (net (code "62") (name "/DMC_PWM") (class "Default")
      (node (ref "R19") (pin "1") (pinfunction "1_1") (pintype "passive"))
      (node (ref "U1") (pin "100") (pinfunction "IO61_100") (pintype "bidirectional"))
    )
    (net (code "63") (name "/JOYDATA1") (class "Default")
      (node (ref "R31") (pin "2") (pinfunction "2_2") (pintype "passive"))
      (node (ref "U13") (pin "2") (pinfunction "A_2") (pintype "input"))
      (node (ref "X2") (pin "8") (pinfunction "F_8") (pintype "passive"))
    )
    (net (code "64") (name "/JOYDATA2") (class "Default")
      (node (ref "R33") (pin "2") (pinfunction "2_2") (pintype "passive"))
      (node (ref "U14") (pin "2") (pinfunction "A_2") (pintype "input"))
      (node (ref "X4") (pin "8") (pinfunction "F_8") (pintype "passive"))
    )
    (net (code "65") (name "/LCH") (class "Default")
      (node (ref "C52") (pin "-") (pinfunction "-_-") (pintype "passive"))
      (node (ref "JP4") (pin "3") (pinfunction "3_3") (pintype "passive"))
    )
    (net (code "66") (name "/LE") (class "Default")
      (node (ref "U10") (pin "4") (pinfunction "Y_4") (pintype "tri_state"))
      (node (ref "X2") (pin "12") (pinfunction "F_12") (pintype "passive"))
      (node (ref "X4") (pin "12") (pinfunction "F_12") (pintype "passive"))
    )
    (net (code "67") (name "/LE_FPGA") (class "Default")
      (node (ref "U1") (pin "20") (pinfunction "IO6_20") (pintype "bidirectional"))
      (node (ref "U10") (pin "2") (pinfunction "A_2") (pintype "input"))
    )
    (net (code "68") (name "/M2") (class "Default")
      (node (ref "CN1") (pin "B2") (pinfunction "M2_B2") (pintype "input"))
      (node (ref "RN1") (pin "8") (pinfunction "2_8") (pintype "passive"))
    )
    (net (code "69") (name "/M2_FPGA") (class "Default")
      (node (ref "RN1") (pin "1") (pinfunction "1_1") (pintype "passive"))
      (node (ref "U1") (pin "98") (pinfunction "IO59_98") (pintype "bidirectional"))
      (node (ref "U11") (pin "2") (pinfunction "A_2") (pintype "input"))
      (node (ref "U12") (pin "2") (pinfunction "A_2") (pintype "input"))
    )
    (net (code "70") (name "/PA0") (class "Default")
      (node (ref "CN1") (pin "A25") (pinfunction "PA0_A25") (pintype "input"))
      (node (ref "U3") (pin "19") (pinfunction "Q8_19") (pintype "output"))
    )
    (net (code "71") (name "/PA1") (class "Default")
      (node (ref "CN1") (pin "A24") (pinfunction "PA1_A24") (pintype "input"))
      (node (ref "U3") (pin "15") (pinfunction "Q6_15") (pintype "output"))
    )
    (net (code "72") (name "/PA2") (class "Default")
      (node (ref "CN1") (pin "A23") (pinfunction "PA2_A23") (pintype "input"))
      (node (ref "U3") (pin "9") (pinfunction "Q4_9") (pintype "output"))
    )
    (net (code "73") (name "/PA3") (class "Default")
      (node (ref "CN1") (pin "A22") (pinfunction "PA3_A22") (pintype "input"))
      (node (ref "U3") (pin "5") (pinfunction "Q2_5") (pintype "output"))
    )
    (net (code "74") (name "/PA4") (class "Default")
      (node (ref "CN1") (pin "A21") (pinfunction "PA4_A21") (pintype "input"))
      (node (ref "U3") (pin "2") (pinfunction "Q1_2") (pintype "output"))
    )
    (net (code "75") (name "/PA5") (class "Default")
      (node (ref "CN1") (pin "A20") (pinfunction "PA5_A20") (pintype "input"))
      (node (ref "U3") (pin "6") (pinfunction "Q3_6") (pintype "output"))
    )
    (net (code "76") (name "/PA6") (class "Default")
      (node (ref "CN1") (pin "A19") (pinfunction "PA6_A19") (pintype "input"))
      (node (ref "U3") (pin "12") (pinfunction "Q5_12") (pintype "output"))
    )
    (net (code "77") (name "/PA7") (class "Default")
      (node (ref "CN1") (pin "B20") (pinfunction "PA7_B20") (pintype "input"))
      (node (ref "U3") (pin "16") (pinfunction "Q7_16") (pintype "output"))
    )
    (net (code "78") (name "/PA8") (class "Default")
      (node (ref "RN7") (pin "8") (pinfunction "2_8") (pintype "passive"))
      (node (ref "U1") (pin "50") (pinfunction "IO28_50") (pintype "bidirectional"))
    )
    (net (code "79") (name "/PA9") (class "Default")
      (node (ref "RN7") (pin "7") (pinfunction "2_7") (pintype "passive"))
      (node (ref "U1") (pin "49") (pinfunction "IO27_49") (pintype "bidirectional"))
    )
    (net (code "80") (name "/PA10") (class "Default")
      (node (ref "RN7") (pin "6") (pinfunction "2_6") (pintype "passive"))
      (node (ref "U1") (pin "48") (pinfunction "IO26_48") (pintype "bidirectional"))
    )
    (net (code "81") (name "/PA11") (class "Default")
      (node (ref "RN7") (pin "5") (pinfunction "2_5") (pintype "passive"))
      (node (ref "U1") (pin "47") (pinfunction "IO25_47") (pintype "bidirectional"))
    )
    (net (code "82") (name "/PA12") (class "Default")
      (node (ref "R1") (pin "2") (pinfunction "2_2") (pintype "passive"))
      (node (ref "U1") (pin "41") (pinfunction "IO23_41") (pintype "bidirectional"))
    )
    (net (code "83") (name "/PA13") (class "Default")
      (node (ref "CN1") (pin "B26") (pinfunction "PA13_B26") (pintype "input"))
      (node (ref "U1") (pin "40") (pinfunction "IO22_40") (pintype "bidirectional"))
      (node (ref "U6") (pin "2") (pinfunction "IN_2") (pintype "input"))
    )
    (net (code "84") (name "/PD0") (class "Default")
      (node (ref "CN1") (pin "A26") (pinfunction "PD0_A26") (pintype "bidirectional"))
      (node (ref "U2") (pin "21") (pinfunction "B0_21") (pintype "bidirectional"))
      (node (ref "U3") (pin "18") (pinfunction "D8_18") (pintype "input"))
    )
    (net (code "85") (name "/PD0_FPGA") (class "Default")
      (node (ref "RN5") (pin "1") (pinfunction "1_1") (pintype "passive"))
      (node (ref "U1") (pin "39") (pinfunction "IO21_39") (pintype "bidirectional"))
    )
    (net (code "86") (name "/PD1") (class "Default")
      (node (ref "CN1") (pin "A27") (pinfunction "PD1_A27") (pintype "bidirectional"))
      (node (ref "U2") (pin "19") (pinfunction "B2_19") (pintype "bidirectional"))
      (node (ref "U3") (pin "14") (pinfunction "D6_14") (pintype "input"))
    )
    (net (code "87") (name "/PD1_FPGA") (class "Default")
      (node (ref "RN5") (pin "3") (pinfunction "1_3") (pintype "passive"))
      (node (ref "U1") (pin "37") (pinfunction "IO19_37") (pintype "bidirectional"))
    )
    (net (code "88") (name "/PD2") (class "Default")
      (node (ref "CN1") (pin "A28") (pinfunction "PD2_A28") (pintype "bidirectional"))
      (node (ref "U2") (pin "17") (pinfunction "B4_17") (pintype "bidirectional"))
      (node (ref "U3") (pin "8") (pinfunction "D4_8") (pintype "input"))
    )
    (net (code "89") (name "/PD2_FPGA") (class "Default")
      (node (ref "RN6") (pin "1") (pinfunction "1_1") (pintype "passive"))
      (node (ref "U1") (pin "35") (pinfunction "IO17_35") (pintype "bidirectional"))
    )
    (net (code "90") (name "/PD3") (class "Default")
      (node (ref "CN1") (pin "A29") (pinfunction "PD3_A29") (pintype "bidirectional"))
      (node (ref "U2") (pin "15") (pinfunction "B6_15") (pintype "bidirectional"))
      (node (ref "U3") (pin "4") (pinfunction "D2_4") (pintype "input"))
    )
    (net (code "91") (name "/PD3_FPGA") (class "Default")
      (node (ref "RN6") (pin "3") (pinfunction "1_3") (pintype "passive"))
      (node (ref "U1") (pin "29") (pinfunction "IO15_29") (pintype "bidirectional"))
    )
    (net (code "92") (name "/PD4") (class "Default")
      (node (ref "CN1") (pin "B30") (pinfunction "PD4_B30") (pintype "bidirectional"))
      (node (ref "U2") (pin "14") (pinfunction "B7_14") (pintype "bidirectional"))
      (node (ref "U3") (pin "3") (pinfunction "D1_3") (pintype "input"))
    )
    (net (code "93") (name "/PD4_FPGA") (class "Default")
      (node (ref "RN6") (pin "4") (pinfunction "1_4") (pintype "passive"))
      (node (ref "U1") (pin "28") (pinfunction "IO14_28") (pintype "bidirectional"))
    )
    (net (code "94") (name "/PD5") (class "Default")
      (node (ref "CN1") (pin "B29") (pinfunction "PD5_B29") (pintype "bidirectional"))
      (node (ref "U2") (pin "16") (pinfunction "B5_16") (pintype "bidirectional"))
      (node (ref "U3") (pin "7") (pinfunction "D3_7") (pintype "input"))
    )
    (net (code "95") (name "/PD5_FPGA") (class "Default")
      (node (ref "RN6") (pin "2") (pinfunction "1_2") (pintype "passive"))
      (node (ref "U1") (pin "34") (pinfunction "IO16_34") (pintype "bidirectional"))
    )
    (net (code "96") (name "/PD6") (class "Default")
      (node (ref "CN1") (pin "B28") (pinfunction "PD6_B28") (pintype "bidirectional"))
      (node (ref "U2") (pin "18") (pinfunction "B3_18") (pintype "bidirectional"))
      (node (ref "U3") (pin "13") (pinfunction "D5_13") (pintype "input"))
    )
    (net (code "97") (name "/PD6_FPGA") (class "Default")
      (node (ref "RN5") (pin "4") (pinfunction "1_4") (pintype "passive"))
      (node (ref "U1") (pin "36") (pinfunction "IO18_36") (pintype "bidirectional"))
    )
    (net (code "98") (name "/PD7") (class "Default")
      (node (ref "CN1") (pin "B27") (pinfunction "PD7_B27") (pintype "bidirectional"))
      (node (ref "U2") (pin "20") (pinfunction "B1_20") (pintype "bidirectional"))
      (node (ref "U3") (pin "17") (pinfunction "D7_17") (pintype "input"))
    )
    (net (code "99") (name "/PD7_FPGA") (class "Default")
      (node (ref "RN5") (pin "2") (pinfunction "1_2") (pintype "passive"))
      (node (ref "U1") (pin "38") (pinfunction "IO20_38") (pintype "bidirectional"))
    )
    (net (code "100") (name "/RCH") (class "Default")
      (node (ref "C51") (pin "-") (pinfunction "-_-") (pintype "passive"))
      (node (ref "JP4") (pin "2") (pinfunction "2_2") (pintype "passive"))
    )
    (net (code "101") (name "/R{slash}W") (class "Default")
      (node (ref "CN1") (pin "A14") (pinfunction "R/W_A14") (pintype "input"))
      (node (ref "U1") (pin "55") (pinfunction "IO33_55") (pintype "bidirectional"))
    )
    (net (code "102") (name "/SCK1") (class "Default")
      (node (ref "R32") (pin "2") (pinfunction "2_2") (pintype "passive"))
      (node (ref "U11") (pin "4") (pinfunction "Y_4") (pintype "tri_state"))
      (node (ref "X2") (pin "9") (pinfunction "F_9") (pintype "passive"))
    )
    (net (code "103") (name "/SCK2") (class "Default")
      (node (ref "R34") (pin "2") (pinfunction "2_2") (pintype "passive"))
      (node (ref "U12") (pin "4") (pinfunction "Y_4") (pintype "tri_state"))
      (node (ref "X4") (pin "9") (pinfunction "F_9") (pintype "passive"))
    )
    (net (code "104") (name "/SND") (class "Default")
      (node (ref "C42") (pin "2") (pinfunction "2_2") (pintype "passive"))
      (node (ref "R21") (pin "2") (pinfunction "2_2") (pintype "passive"))
      (node (ref "R22") (pin "1") (pinfunction "1_1") (pintype "passive"))
      (node (ref "R23") (pin "1") (pinfunction "1_1") (pintype "passive"))
      (node (ref "R29") (pin "1") (pinfunction "1_1") (pintype "passive"))
    )
    (net (code "105") (name "/SNDO") (class "Default")
      (node (ref "R21") (pin "1") (pinfunction "1_1") (pintype "passive"))
      (node (ref "U1") (pin "99") (pinfunction "IO60_99") (pintype "bidirectional"))
    )
    (net (code "106") (name "/SND_EXT") (class "Default")
      (node (ref "CN1") (pin "B15") (pinfunction "SNDI_B15") (pintype "bidirectional"))
      (node (ref "CN1") (pin "B16") (pinfunction "SNDO_B16") (pintype "bidirectional"))
      (node (ref "R25") (pin "1") (pinfunction "1_1") (pintype "passive"))
      (node (ref "R26") (pin "1") (pinfunction "1_1") (pintype "passive"))
      (node (ref "R27") (pin "1") (pinfunction "1_1") (pintype "passive"))
    )
    (net (code "107") (name "/TCK") (class "Default")
      (node (ref "RN8") (pin "7") (pinfunction "2_7") (pintype "passive"))
      (node (ref "U1") (pin "62") (pinfunction "TCK_62") (pintype "input"))
      (node (ref "X1") (pin "1") (pinfunction "S_1") (pintype "passive"))
    )
    (net (code "108") (name "/TDI") (class "Default")
      (node (ref "RN8") (pin "5") (pinfunction "2_5") (pintype "passive"))
      (node (ref "U1") (pin "67") (pinfunction "TDI_67") (pintype "input"))
      (node (ref "X1") (pin "9") (pinfunction "S_9") (pintype "passive"))
    )
    (net (code "109") (name "/TDO") (class "Default")
      (node (ref "U1") (pin "64") (pinfunction "TDO_64") (pintype "output"))
      (node (ref "X1") (pin "3") (pinfunction "S_3") (pintype "passive"))
    )
    (net (code "110") (name "/TMS") (class "Default")
      (node (ref "RN8") (pin "6") (pinfunction "2_6") (pintype "passive"))
      (node (ref "U1") (pin "63") (pinfunction "TMS_63") (pintype "input"))
      (node (ref "X1") (pin "5") (pinfunction "S_5") (pintype "passive"))
    )
    (net (code "111") (name "/VA10") (class "Default")
      (node (ref "CN1") (pin "A18") (pinfunction "VA10_A18") (pintype "output"))
      (node (ref "R18") (pin "2") (pinfunction "2_2") (pintype "passive"))
    )
    (net (code "112") (name "/VCCA") (class "Default")
      (node (ref "C10") (pin "+") (pinfunction "+_+") (pintype "passive"))
      (node (ref "C43") (pin "2") (pinfunction "2_2") (pintype "passive"))
      (node (ref "C9") (pin "1") (pinfunction "1_1") (pintype "passive"))
      (node (ref "U9") (pin "4") (pinfunction "VS+_4") (pintype "power_in"))
      (node (ref "VR1") (pin "1") (pinfunction "VO_1") (pintype "passive"))
    )
    (net (code "113") (name "/{slash}CSO") (class "Default")
      (node (ref "U1") (pin "6") (pinfunction "/CSO_6") (pintype "bidirectional"))
      (node (ref "U7") (pin "1") (pinfunction "/CS_1") (pintype "input"))
    )
    (net (code "114") (name "/{slash}DENDY") (class "Default")
      (node (ref "J2") (pin "1") (pinfunction "1_1") (pintype "passive"))
      (node (ref "U1") (pin "3") (pinfunction "IO3_3") (pintype "bidirectional"))
    )
    (net (code "115") (name "/{slash}IN0") (class "Default")
      (node (ref "U1") (pin "2") (pinfunction "IO2_2") (pintype "bidirectional"))
      (node (ref "U11") (pin "1") (pinfunction "/OE_1") (pintype "bidirectional"))
      (node (ref "U13") (pin "1") (pinfunction "/OE_1") (pintype "bidirectional"))
    )
    (net (code "116") (name "/{slash}IN1") (class "Default")
      (node (ref "U1") (pin "4") (pinfunction "IO4_4") (pintype "bidirectional"))
      (node (ref "U12") (pin "1") (pinfunction "/OE_1") (pintype "bidirectional"))
      (node (ref "U14") (pin "1") (pinfunction "/OE_1") (pintype "bidirectional"))
    )
    (net (code "117") (name "/{slash}IRQ") (class "Default")
      (node (ref "CN1") (pin "A15") (pinfunction "/IRQ_A15") (pintype "bidirectional"))
      (node (ref "R3") (pin "2") (pinfunction "2_2") (pintype "passive"))
      (node (ref "U5") (pin "3") (pinfunction "IN2_3") (pintype "input"))
    )
    (net (code "118") (name "/{slash}IRQ_FPGA") (class "Default")
      (node (ref "U1") (pin "66") (pinfunction "CLK2_66") (pintype "input"))
      (node (ref "U5") (pin "4") (pinfunction "OUT2_4") (pintype "output"))
    )
    (net (code "119") (name "/{slash}PA13") (class "Default")
      (node (ref "CN1") (pin "B19") (pinfunction "/PA13_B19") (pintype "input"))
      (node (ref "U6") (pin "4") (pinfunction "OUT_4") (pintype "output"))
    )
    (net (code "120") (name "/{slash}PAL") (class "Default")
      (node (ref "J1") (pin "1") (pinfunction "1_1") (pintype "passive"))
      (node (ref "U1") (pin "1") (pinfunction "IO1_1") (pintype "bidirectional"))
      (node (ref "U8") (pin "6") (pinfunction "S_6") (pintype "input"))
    )
    (net (code "121") (name "/{slash}PRD") (class "Default")
      (node (ref "CN1") (pin "A17") (pinfunction "/PRD_A17") (pintype "input"))
      (node (ref "R17") (pin "2") (pinfunction "2_2") (pintype "passive"))
    )
    (net (code "122") (name "/{slash}PRD_FPGA") (class "Default")
      (node (ref "R17") (pin "1") (pinfunction "1_1") (pintype "passive"))
      (node (ref "U1") (pin "53") (pinfunction "IO31_53") (pintype "bidirectional"))
      (node (ref "U2") (pin "2") (pinfunction "DIR_2") (pintype "input"))
    )
    (net (code "123") (name "/{slash}PWR") (class "Default")
      (node (ref "CN1") (pin "B17") (pinfunction "/PWR_B17") (pintype "input"))
      (node (ref "U1") (pin "52") (pinfunction "IO30_52") (pintype "bidirectional"))
    )
    (net (code "124") (name "/{slash}RESET") (class "Default")
      (node (ref "C29") (pin "2") (pinfunction "2_2") (pintype "passive"))
      (node (ref "J3") (pin "1") (pinfunction "1_1") (pintype "passive"))
      (node (ref "U1") (pin "5") (pinfunction "IO5_5") (pintype "bidirectional"))
    )
    (net (code "125") (name "/{slash}ROMSEL") (class "Default")
      (node (ref "CN1") (pin "B14") (pinfunction "/ROMSEL_B14") (pintype "input"))
      (node (ref "U1") (pin "54") (pinfunction "IO32_54") (pintype "bidirectional"))
    )
    (net (code "126") (name "/{slash}VCS_FPGA") (class "Default")
      (node (ref "U1") (pin "57") (pinfunction "IO35_57") (pintype "bidirectional"))
      (node (ref "U5") (pin "6") (pinfunction "OUT1_6") (pintype "output"))
    )
    (net (code "127") (name "/{slash}VRAMSC") (class "Default")
      (node (ref "CN1") (pin "B18") (pinfunction "VRAMCS_B18") (pintype "output"))
      (node (ref "U5") (pin "1") (pinfunction "IN1_1") (pintype "input"))
    )
    (net (code "128") (name "GND") (class "Default")
      (node (ref "C1") (pin "1") (pinfunction "1_1") (pintype "passive"))
      (node (ref "C10") (pin "-") (pinfunction "-_-") (pintype "passive"))
      (node (ref "C11") (pin "-") (pinfunction "-_-") (pintype "passive"))
      (node (ref "C12") (pin "2") (pinfunction "2_2") (pintype "passive"))
      (node (ref "C13") (pin "2") (pinfunction "2_2") (pintype "passive"))
      (node (ref "C14") (pin "-") (pinfunction "-_-") (pintype "passive"))
      (node (ref "C15") (pin "2") (pinfunction "2_2") (pintype "passive"))
      (node (ref "C16") (pin "2") (pinfunction "2_2") (pintype "passive"))
      (node (ref "C17") (pin "2") (pinfunction "2_2") (pintype "passive"))
      (node (ref "C18") (pin "2") (pinfunction "2_2") (pintype "passive"))
      (node (ref "C19") (pin "-") (pinfunction "-_-") (pintype "passive"))
      (node (ref "C2") (pin "2") (pinfunction "2_2") (pintype "passive"))
      (node (ref "C20") (pin "1") (pinfunction "1_1") (pintype "passive"))
      (node (ref "C21") (pin "2") (pinfunction "2_2") (pintype "passive"))
      (node (ref "C22") (pin "1") (pinfunction "1_1") (pintype "passive"))
      (node (ref "C23") (pin "1") (pinfunction "1_1") (pintype "passive"))
      (node (ref "C24") (pin "2") (pinfunction "2_2") (pintype "passive"))
      (node (ref "C25") (pin "2") (pinfunction "2_2") (pintype "passive"))
      (node (ref "C26") (pin "1") (pinfunction "1_1") (pintype "passive"))
      (node (ref "C27") (pin "1") (pinfunction "1_1") (pintype "passive"))
      (node (ref "C28") (pin "1") (pinfunction "1_1") (pintype "passive"))
      (node (ref "C29") (pin "1") (pinfunction "1_1") (pintype "passive"))
      (node (ref "C3") (pin "1") (pinfunction "1_1") (pintype "passive"))
      (node (ref "C30") (pin "2") (pinfunction "2_2") (pintype "passive"))
      (node (ref "C31") (pin "2") (pinfunction "2_2") (pintype "passive"))
      (node (ref "C32") (pin "1") (pinfunction "1_1") (pintype "passive"))
      (node (ref "C33") (pin "1") (pinfunction "1_1") (pintype "passive"))
      (node (ref "C34") (pin "2") (pinfunction "2_2") (pintype "passive"))
      (node (ref "C35") (pin "2") (pinfunction "2_2") (pintype "passive"))
      (node (ref "C36") (pin "2") (pinfunction "2_2") (pintype "passive"))
      (node (ref "C37") (pin "2") (pinfunction "2_2") (pintype "passive"))
      (node (ref "C38") (pin "1") (pinfunction "1_1") (pintype "passive"))
      (node (ref "C39") (pin "1") (pinfunction "1_1") (pintype "passive"))
      (node (ref "C4") (pin "1") (pinfunction "1_1") (pintype "passive"))
      (node (ref "C40") (pin "1") (pinfunction "1_1") (pintype "passive"))
      (node (ref "C41") (pin "1") (pinfunction "1_1") (pintype "passive"))
      (node (ref "C42") (pin "1") (pinfunction "1_1") (pintype "passive"))
      (node (ref "C43") (pin "1") (pinfunction "1_1") (pintype "passive"))
      (node (ref "C45") (pin "1") (pinfunction "1_1") (pintype "passive"))
      (node (ref "C46") (pin "2") (pinfunction "2_2") (pintype "passive"))
      (node (ref "C47") (pin "2") (pinfunction "2_2") (pintype "passive"))
      (node (ref "C5") (pin "1") (pinfunction "1_1") (pintype "passive"))
      (node (ref "C50") (pin "1") (pinfunction "1_1") (pintype "passive"))
      (node (ref "C53") (pin "2") (pinfunction "2_2") (pintype "passive"))
      (node (ref "C54") (pin "-") (pinfunction "-_-") (pintype "passive"))
      (node (ref "C6") (pin "2") (pinfunction "2_2") (pintype "passive"))
      (node (ref "C7") (pin "2") (pinfunction "2_2") (pintype "passive"))
      (node (ref "C8") (pin "2") (pinfunction "2_2") (pintype "passive"))
      (node (ref "C9") (pin "2") (pinfunction "2_2") (pintype "passive"))
      (node (ref "CN1") (pin "A1") (pinfunction "GND_A1") (pintype "power_in"))
      (node (ref "CN1") (pin "A16") (pinfunction "GND_A16") (pintype "power_in"))
      (node (ref "J1") (pin "2") (pinfunction "2_2") (pintype "passive"))
      (node (ref "J2") (pin "2") (pinfunction "2_2") (pintype "passive"))
      (node (ref "J3") (pin "2") (pinfunction "2_2") (pintype "passive"))
      (node (ref "JP4") (pin "1") (pinfunction "1_1") (pintype "passive"))
      (node (ref "JP5") (pin "1") (pinfunction "1_1") (pintype "passive"))
      (node (ref "JP5") (pin "3") (pinfunction "3_3") (pintype "passive"))
      (node (ref "LED2") (pin "C") (pinfunction "C_C") (pintype "passive"))
      (node (ref "R13") (pin "2") (pinfunction "2_2") (pintype "passive"))
      (node (ref "R20") (pin "2") (pinfunction "2_2") (pintype "passive"))
      (node (ref "R22") (pin "2") (pinfunction "2_2") (pintype "passive"))
      (node (ref "R26") (pin "2") (pinfunction "2_2") (pintype "passive"))
      (node (ref "R40") (pin "2") (pinfunction "2_2") (pintype "passive"))
      (node (ref "R6") (pin "1") (pinfunction "1_1") (pintype "passive"))
      (node (ref "RN12") (pin "1") (pinfunction "1_1") (pintype "passive"))
      (node (ref "RN12") (pin "4") (pinfunction "1_4") (pintype "passive"))
      (node (ref "RN8") (pin "1") (pinfunction "1_1") (pintype "passive"))
      (node (ref "RN8") (pin "2") (pinfunction "1_2") (pintype "passive"))
      (node (ref "RN8") (pin "8") (pinfunction "2_8") (pintype "passive"))
      (node (ref "RN9") (pin "5") (pinfunction "2_5") (pintype "passive"))
      (node (ref "U1") (pin "11") (pinfunction "GNDA_PLL1_11") (pintype "power_in"))
      (node (ref "U1") (pin "14") (pinfunction "MSEL0_14") (pintype "input"))
      (node (ref "U1") (pin "15") (pinfunction "MSEL1_15") (pintype "input"))
      (node (ref "U1") (pin "19") (pinfunction "GND_19") (pintype "power_in"))
      (node (ref "U1") (pin "30") (pinfunction "GND_30") (pintype "power_in"))
      (node (ref "U1") (pin "32") (pinfunction "GND_32") (pintype "power_in"))
      (node (ref "U1") (pin "43") (pinfunction "GND_43") (pintype "power_in"))
      (node (ref "U1") (pin "45") (pinfunction "GND_45") (pintype "power_in"))
      (node (ref "U1") (pin "58") (pinfunction "GND_58") (pintype "power_in"))
      (node (ref "U1") (pin "81") (pinfunction "GND_81") (pintype "power_in"))
      (node (ref "U1") (pin "83") (pinfunction "GND_83") (pintype "power_in"))
      (node (ref "U1") (pin "94") (pinfunction "GND_94") (pintype "power_in"))
      (node (ref "U1") (pin "96") (pinfunction "GND_96") (pintype "power_in"))
      (node (ref "U10") (pin "1") (pinfunction "/OE_1") (pintype "input"))
      (node (ref "U10") (pin "3") (pinfunction "GND_3") (pintype "power_in"))
      (node (ref "U11") (pin "3") (pinfunction "GND_3") (pintype "power_in"))
      (node (ref "U12") (pin "3") (pinfunction "GND_3") (pintype "power_in"))
      (node (ref "U13") (pin "3") (pinfunction "GND_3") (pintype "power_in"))
      (node (ref "U14") (pin "3") (pinfunction "GND_3") (pintype "power_in"))
      (node (ref "U15") (pin "4") (pinfunction "V-_4") (pintype "power_in"))
      (node (ref "U2") (pin "11") (pinfunction "GND_11") (pintype "power_in"))
      (node (ref "U2") (pin "12") (pinfunction "GND_12") (pintype "power_in"))
      (node (ref "U2") (pin "13") (pinfunction "GND_13") (pintype "power_in"))
      (node (ref "U2") (pin "22") (pinfunction "/OE_22") (pintype "input"))
      (node (ref "U3") (pin "1") (pinfunction "/OE_1") (pintype "input"))
      (node (ref "U3") (pin "10") (pinfunction "GND_10") (pintype "power_in"))
      (node (ref "U4") (pin "11") (pinfunction "GND_11") (pintype "power_in"))
      (node (ref "U4") (pin "12") (pinfunction "GND_12") (pintype "power_in"))
      (node (ref "U4") (pin "13") (pinfunction "GND_13") (pintype "power_in"))
      (node (ref "U4") (pin "22") (pinfunction "/OE_22") (pintype "input"))
      (node (ref "U5") (pin "2") (pinfunction "GND_2") (pintype "power_in"))
      (node (ref "U6") (pin "3") (pinfunction "GND_3") (pintype "power_in"))
      (node (ref "U7") (pin "4") (pinfunction "GND_4") (pintype "power_in"))
      (node (ref "U8") (pin "2") (pinfunction "GND_2") (pintype "power_in"))
      (node (ref "U9") (pin "5") (pinfunction "GND_5") (pintype "power_in"))
      (node (ref "VR1") (pin "2") (pinfunction "GND_2") (pintype "passive"))
      (node (ref "VR2") (pin "3") (pinfunction "GND_3") (pintype "passive"))
      (node (ref "VR3") (pin "1") (pinfunction "GND_1") (pintype "power_in"))
      (node (ref "VR4") (pin "1") (pinfunction "GND_1") (pintype "power_in"))
      (node (ref "X1") (pin "10") (pinfunction "S_10") (pintype "passive"))
      (node (ref "X1") (pin "2") (pinfunction "S_2") (pintype "passive"))
      (node (ref "X2") (pin "1") (pinfunction "F_1") (pintype "passive"))
      (node (ref "X3") (pin "2") (pinfunction "2_2") (pintype "passive"))
      (node (ref "X3") (pin "3") (pinfunction "3_3") (pintype "passive"))
      (node (ref "X4") (pin "1") (pinfunction "F_1") (pintype "passive"))
      (node (ref "XO1") (pin "2") (pinfunction "GND_2") (pintype "power_in"))
      (node (ref "XO2") (pin "2") (pinfunction "GND_2") (pintype "power_in"))
    )
    (net (code "129") (name "Net-(C44-Pad+)") (class "Default")
      (node (ref "C44") (pin "+") (pinfunction "+_+") (pintype "passive"))
      (node (ref "R30") (pin "2") (pinfunction "2_2") (pintype "passive"))
    )
    (net (code "130") (name "Net-(C44-Pad-)") (class "Default")
      (node (ref "C44") (pin "-") (pinfunction "-_-") (pintype "passive"))
      (node (ref "JP5") (pin "2") (pinfunction "2_2") (pintype "passive"))
    )
    (net (code "131") (name "Net-(C48-Pad1)") (class "Default")
      (node (ref "C48") (pin "1") (pinfunction "1_1") (pintype "passive"))
      (node (ref "R23") (pin "2") (pinfunction "2_2") (pintype "passive"))
      (node (ref "R24") (pin "2") (pinfunction "2_2") (pintype "passive"))
      (node (ref "R25") (pin "2") (pinfunction "2_2") (pintype "passive"))
    )
    (net (code "132") (name "Net-(C49-Pad1)") (class "Default")
      (node (ref "C49") (pin "1") (pinfunction "1_1") (pintype "passive"))
      (node (ref "R27") (pin "2") (pinfunction "2_2") (pintype "passive"))
      (node (ref "R28") (pin "2") (pinfunction "2_2") (pintype "passive"))
      (node (ref "R29") (pin "2") (pinfunction "2_2") (pintype "passive"))
    )
    (net (code "133") (name "Net-(C51-Pad+)") (class "Default")
      (node (ref "C51") (pin "+") (pinfunction "+_+") (pintype "passive"))
      (node (ref "R35") (pin "2") (pinfunction "2_2") (pintype "passive"))
    )
    (net (code "134") (name "Net-(C52-Pad+)") (class "Default")
      (node (ref "C52") (pin "+") (pinfunction "+_+") (pintype "passive"))
      (node (ref "R38") (pin "2") (pinfunction "2_2") (pintype "passive"))
    )
    (net (code "135") (name "Net-(C53-Pad1)") (class "Default")
      (node (ref "C53") (pin "1") (pinfunction "1_1") (pintype "passive"))
      (node (ref "C54") (pin "+") (pinfunction "+_+") (pintype "passive"))
      (node (ref "R36") (pin "1") (pinfunction "1_1") (pintype "passive"))
      (node (ref "R39") (pin "2") (pinfunction "2_2") (pintype "passive"))
      (node (ref "R40") (pin "1") (pinfunction "1_1") (pintype "passive"))
      (node (ref "R41") (pin "1") (pinfunction "1_1") (pintype "passive"))
    )
    (net (code "136") (name "Net-(CN1-PA8)") (class "Default")
      (node (ref "CN1") (pin "B21") (pinfunction "PA8_B21") (pintype "input"))
      (node (ref "RN7") (pin "1") (pinfunction "1_1") (pintype "passive"))
    )
    (net (code "137") (name "Net-(CN1-PA9)") (class "Default")
      (node (ref "CN1") (pin "B22") (pinfunction "PA9_B22") (pintype "input"))
      (node (ref "RN7") (pin "2") (pinfunction "1_2") (pintype "passive"))
    )
    (net (code "138") (name "Net-(CN1-PA10)") (class "Default")
      (node (ref "CN1") (pin "B23") (pinfunction "PA10_B23") (pintype "input"))
      (node (ref "RN7") (pin "3") (pinfunction "1_3") (pintype "passive"))
    )
    (net (code "139") (name "Net-(CN1-PA11)") (class "Default")
      (node (ref "CN1") (pin "B24") (pinfunction "PA11_B24") (pintype "input"))
      (node (ref "RN7") (pin "4") (pinfunction "1_4") (pintype "passive"))
    )
    (net (code "140") (name "Net-(CN1-PA12)") (class "Default")
      (node (ref "CN1") (pin "B25") (pinfunction "PA12_B25") (pintype "input"))
      (node (ref "R1") (pin "1") (pinfunction "1_1") (pintype "passive"))
    )
    (net (code "141") (name "Net-(D1-PadA)") (class "Default")
      (node (ref "D1") (pin "A") (pinfunction "A_A") (pintype "passive"))
      (node (ref "JP1") (pin "2") (pinfunction "2_2") (pintype "passive"))
    )
    (net (code "142") (name "Net-(JP1-Pad1)") (class "Default")
      (node (ref "JP1") (pin "1") (pinfunction "1_1") (pintype "passive"))
      (node (ref "X3") (pin "1") (pinfunction "1_1") (pintype "passive"))
    )
    (net (code "143") (name "Net-(JP2-Pad1)") (class "Default")
      (node (ref "JP2") (pin "1") (pinfunction "1_1") (pintype "passive"))
      (node (ref "R10") (pin "2") (pinfunction "2_2") (pintype "passive"))
    )
    (net (code "144") (name "Net-(LED2-PadA)") (class "Default")
      (node (ref "LED2") (pin "A") (pinfunction "A_A") (pintype "passive"))
      (node (ref "R4") (pin "1") (pinfunction "1_1") (pintype "passive"))
    )
    (net (code "145") (name "Net-(R8-Pad2)") (class "Default")
      (node (ref "R8") (pin "2") (pinfunction "2_2") (pintype "passive"))
      (node (ref "U8") (pin "1") (pinfunction "1_1") (pintype "input"))
    )
    (net (code "146") (name "Net-(RN5A-2)") (class "Default")
      (node (ref "RN5") (pin "8") (pinfunction "2_8") (pintype "passive"))
      (node (ref "U2") (pin "3") (pinfunction "A0_3") (pintype "bidirectional"))
    )
    (net (code "147") (name "Net-(RN5B-2)") (class "Default")
      (node (ref "RN5") (pin "7") (pinfunction "2_7") (pintype "passive"))
      (node (ref "U2") (pin "4") (pinfunction "A1_4") (pintype "bidirectional"))
    )
    (net (code "148") (name "Net-(RN5C-2)") (class "Default")
      (node (ref "RN5") (pin "6") (pinfunction "2_6") (pintype "passive"))
      (node (ref "U2") (pin "5") (pinfunction "A2_5") (pintype "bidirectional"))
    )
    (net (code "149") (name "Net-(RN5D-2)") (class "Default")
      (node (ref "RN5") (pin "5") (pinfunction "2_5") (pintype "passive"))
      (node (ref "U2") (pin "6") (pinfunction "A3_6") (pintype "bidirectional"))
    )
    (net (code "150") (name "Net-(RN6A-2)") (class "Default")
      (node (ref "RN6") (pin "8") (pinfunction "2_8") (pintype "passive"))
      (node (ref "U2") (pin "7") (pinfunction "A4_7") (pintype "bidirectional"))
    )
    (net (code "151") (name "Net-(RN6B-2)") (class "Default")
      (node (ref "RN6") (pin "7") (pinfunction "2_7") (pintype "passive"))
      (node (ref "U2") (pin "8") (pinfunction "A5_8") (pintype "bidirectional"))
    )
    (net (code "152") (name "Net-(RN6C-2)") (class "Default")
      (node (ref "RN6") (pin "6") (pinfunction "2_6") (pintype "passive"))
      (node (ref "U2") (pin "9") (pinfunction "A6_9") (pintype "bidirectional"))
    )
    (net (code "153") (name "Net-(RN6D-2)") (class "Default")
      (node (ref "RN6") (pin "5") (pinfunction "2_5") (pintype "passive"))
      (node (ref "U2") (pin "10") (pinfunction "A7_10") (pintype "bidirectional"))
    )
    (net (code "154") (name "Net-(RN9B-1)") (class "Default")
      (node (ref "R11") (pin "1") (pinfunction "1_1") (pintype "passive"))
      (node (ref "R12") (pin "2") (pinfunction "2_2") (pintype "passive"))
      (node (ref "RN9") (pin "2") (pinfunction "1_2") (pintype "passive"))
    )
    (net (code "155") (name "Net-(RN9C-1)") (class "Default")
      (node (ref "R11") (pin "2") (pinfunction "2_2") (pintype "passive"))
      (node (ref "RN9") (pin "3") (pinfunction "1_3") (pintype "passive"))
      (node (ref "RN9") (pin "4") (pinfunction "1_4") (pintype "passive"))
    )
    (net (code "156") (name "Net-(RN10B-1)") (class "Default")
      (node (ref "RN10") (pin "2") (pinfunction "1_2") (pintype "passive"))
      (node (ref "RN11") (pin "1") (pinfunction "1_1") (pintype "passive"))
      (node (ref "RN11") (pin "7") (pinfunction "2_7") (pintype "passive"))
    )
    (net (code "157") (name "Net-(RN10C-1)") (class "Default")
      (node (ref "RN10") (pin "3") (pinfunction "1_3") (pintype "passive"))
      (node (ref "RN11") (pin "2") (pinfunction "1_2") (pintype "passive"))
      (node (ref "RN11") (pin "6") (pinfunction "2_6") (pintype "passive"))
    )
    (net (code "158") (name "Net-(RN10D-1)") (class "Default")
      (node (ref "RN10") (pin "4") (pinfunction "1_4") (pintype "passive"))
      (node (ref "RN11") (pin "3") (pinfunction "1_3") (pintype "passive"))
      (node (ref "RN11") (pin "5") (pinfunction "2_5") (pintype "passive"))
    )
    (net (code "159") (name "Net-(RN11A-2)") (class "Default")
      (node (ref "R14") (pin "1") (pinfunction "1_1") (pintype "passive"))
      (node (ref "RN10") (pin "1") (pinfunction "1_1") (pintype "passive"))
      (node (ref "RN11") (pin "8") (pinfunction "2_8") (pintype "passive"))
    )
    (net (code "160") (name "Net-(RN11D-1)") (class "Default")
      (node (ref "R12") (pin "1") (pinfunction "1_1") (pintype "passive"))
      (node (ref "RN11") (pin "4") (pinfunction "1_4") (pintype "passive"))
      (node (ref "RN9") (pin "1") (pinfunction "1_1") (pintype "passive"))
    )
    (net (code "161") (name "Net-(RN12A-2)") (class "Default")
      (node (ref "C49") (pin "2") (pinfunction "2_2") (pintype "passive"))
      (node (ref "RN12") (pin "2") (pinfunction "1_2") (pintype "passive"))
      (node (ref "RN12") (pin "8") (pinfunction "2_8") (pintype "passive"))
      (node (ref "U15") (pin "5") (pinfunction "+IN_5") (pintype "input"))
    )
    (net (code "162") (name "Net-(RN12C-1)") (class "Default")
      (node (ref "C48") (pin "2") (pinfunction "2_2") (pintype "passive"))
      (node (ref "RN12") (pin "3") (pinfunction "1_3") (pintype "passive"))
      (node (ref "RN12") (pin "5") (pinfunction "2_5") (pintype "passive"))
      (node (ref "U15") (pin "3") (pinfunction "+IN_3") (pintype "input"))
    )
    (net (code "163") (name "Net-(U1-CONF_DONE)") (class "Default")
      (node (ref "R16") (pin "1") (pinfunction "1_1") (pintype "passive"))
      (node (ref "U1") (pin "60") (pinfunction "CONF_DONE_60") (pintype "bidirectional"))
    )
    (net (code "164") (name "Net-(U1-IO29)") (class "Default")
      (node (ref "R18") (pin "1") (pinfunction "1_1") (pintype "passive"))
      (node (ref "U1") (pin "51") (pinfunction "IO29_51") (pintype "bidirectional"))
    )
    (net (code "165") (name "Net-(U1-VCCA_PLL1)") (class "Default")
      (node (ref "C26") (pin "2") (pinfunction "2_2") (pintype "passive"))
      (node (ref "C27") (pin "2") (pinfunction "2_2") (pintype "passive"))
      (node (ref "C28") (pin "2") (pinfunction "2_2") (pintype "passive"))
      (node (ref "L1") (pin "2") (pinfunction "2_2") (pintype "passive"))
      (node (ref "U1") (pin "9") (pinfunction "VCCA_PLL1_9") (pintype "power_in"))
    )
    (net (code "166") (name "Net-(U1-{slash}CE)") (class "Default")
      (node (ref "R6") (pin "2") (pinfunction "2_2") (pintype "passive"))
      (node (ref "U1") (pin "13") (pinfunction "/CE_13") (pintype "input"))
    )
    (net (code "167") (name "Net-(U1-{slash}CONFIG)") (class "Default")
      (node (ref "R5") (pin "2") (pinfunction "2_2") (pintype "passive"))
      (node (ref "U1") (pin "8") (pinfunction "/CONFIG_8") (pintype "bidirectional"))
    )
    (net (code "168") (name "Net-(U1-{slash}STATUS)") (class "Default")
      (node (ref "R15") (pin "1") (pinfunction "1_1") (pintype "passive"))
      (node (ref "U1") (pin "61") (pinfunction "/STATUS_61") (pintype "bidirectional"))
    )
    (net (code "169") (name "Net-(U3-EN)") (class "Default")
      (node (ref "R2") (pin "2") (pinfunction "2_2") (pintype "passive"))
      (node (ref "U3") (pin "11") (pinfunction "EN_11") (pintype "input"))
    )
    (net (code "170") (name "Net-(U8-0)") (class "Default")
      (node (ref "R7") (pin "2") (pinfunction "2_2") (pintype "passive"))
      (node (ref "U8") (pin "3") (pinfunction "0_3") (pintype "input"))
    )
    (net (code "171") (name "Net-(U8-Z)") (class "Default")
      (node (ref "R10") (pin "1") (pinfunction "1_1") (pintype "passive"))
      (node (ref "R9") (pin "1") (pinfunction "1_1") (pintype "passive"))
      (node (ref "U8") (pin "4") (pinfunction "Z_4") (pintype "output"))
    )
    (net (code "172") (name "Net-(U9-CH1_IN)") (class "Default")
      (node (ref "R13") (pin "1") (pinfunction "1_1") (pintype "passive"))
      (node (ref "R14") (pin "2") (pinfunction "2_2") (pintype "passive"))
      (node (ref "U9") (pin "1") (pinfunction "CH1_IN_1") (pintype "input"))
      (node (ref "U9") (pin "2") (pinfunction "CH2_IN_2") (pintype "input"))
      (node (ref "U9") (pin "3") (pinfunction "CH3_IN_3") (pintype "input"))
    )
    (net (code "173") (name "Net-(U9-CH3_OUT)") (class "Default")
      (node (ref "R30") (pin "1") (pinfunction "1_1") (pintype "passive"))
      (node (ref "U9") (pin "6") (pinfunction "CH3_OUT_6") (pintype "output"))
    )
    (net (code "174") (name "Net-(U15A--IN)") (class "Default")
      (node (ref "R36") (pin "2") (pinfunction "2_2") (pintype "passive"))
      (node (ref "R37") (pin "1") (pinfunction "1_1") (pintype "passive"))
      (node (ref "U15") (pin "2") (pinfunction "-IN_2") (pintype "input"))
    )
    (net (code "175") (name "Net-(U15A-OUT)") (class "Default")
      (node (ref "R35") (pin "1") (pinfunction "1_1") (pintype "passive"))
      (node (ref "R37") (pin "2") (pinfunction "2_2") (pintype "passive"))
      (node (ref "U15") (pin "1") (pinfunction "OUT_1") (pintype "output"))
    )
    (net (code "176") (name "Net-(U15B--IN)") (class "Default")
      (node (ref "R41") (pin "2") (pinfunction "2_2") (pintype "passive"))
      (node (ref "R42") (pin "1") (pinfunction "1_1") (pintype "passive"))
      (node (ref "U15") (pin "6") (pinfunction "-IN_6") (pintype "input"))
    )
    (net (code "177") (name "Net-(U15B-OUT)") (class "Default")
      (node (ref "R38") (pin "1") (pinfunction "1_1") (pintype "passive"))
      (node (ref "R42") (pin "2") (pinfunction "2_2") (pintype "passive"))
      (node (ref "U15") (pin "7") (pinfunction "OUT_7") (pintype "output"))
    )
    (net (code "178") (name "Net-(XO1-OUT)") (class "Default")
      (node (ref "R8") (pin "1") (pinfunction "1_1") (pintype "passive"))
      (node (ref "XO1") (pin "3") (pinfunction "OUT_3") (pintype "output"))
    )
    (net (code "179") (name "Net-(XO2-OUT)") (class "Default")
      (node (ref "R7") (pin "1") (pinfunction "1_1") (pintype "passive"))
      (node (ref "XO2") (pin "3") (pinfunction "OUT_3") (pintype "output"))
    )
    (net (code "180") (name "VCC") (class "Default")
      (node (ref "C11") (pin "+") (pinfunction "+_+") (pintype "passive"))
      (node (ref "C12") (pin "1") (pinfunction "1_1") (pintype "passive"))
      (node (ref "C50") (pin "2") (pinfunction "2_2") (pintype "passive"))
      (node (ref "C8") (pin "1") (pinfunction "1_1") (pintype "passive"))
      (node (ref "D1") (pin "C") (pinfunction "C_C") (pintype "passive"))
      (node (ref "R39") (pin "1") (pinfunction "1_1") (pintype "passive"))
      (node (ref "RN12") (pin "6") (pinfunction "2_6") (pintype "passive"))
      (node (ref "RN12") (pin "7") (pinfunction "2_7") (pintype "passive"))
      (node (ref "U15") (pin "8") (pinfunction "V+_8") (pintype "power_in"))
      (node (ref "VR1") (pin "3") (pinfunction "VI_3") (pintype "input"))
      (node (ref "VR2") (pin "1") (pinfunction "VI_1") (pintype "input"))
    )
    (net (code "181") (name "VCCINT") (class "Default")
      (node (ref "C18") (pin "1") (pinfunction "1_1") (pintype "passive"))
      (node (ref "C19") (pin "+") (pinfunction "+_+") (pintype "passive"))
      (node (ref "C24") (pin "1") (pinfunction "1_1") (pintype "passive"))
      (node (ref "C25") (pin "1") (pinfunction "1_1") (pintype "passive"))
      (node (ref "C32") (pin "2") (pinfunction "2_2") (pintype "passive"))
      (node (ref "C33") (pin "2") (pinfunction "2_2") (pintype "passive"))
      (node (ref "L1") (pin "1") (pinfunction "1_1") (pintype "passive"))
      (node (ref "U1") (pin "33") (pinfunction "VCC_INT_33") (pintype "power_in"))
      (node (ref "U1") (pin "44") (pinfunction "VCC_INT_44") (pintype "power_in"))
      (node (ref "U1") (pin "82") (pinfunction "VCC_INT_82") (pintype "power_in"))
      (node (ref "U1") (pin "93") (pinfunction "VCC_INT_93") (pintype "power_in"))
      (node (ref "VR4") (pin "2") (pinfunction "VOUT_2") (pintype "power_in"))
    )
    (net (code "182") (name "VCCIO") (class "Default")
      (node (ref "C16") (pin "1") (pinfunction "1_1") (pintype "passive"))
      (node (ref "C17") (pin "1") (pinfunction "1_1") (pintype "passive"))
      (node (ref "C21") (pin "1") (pinfunction "1_1") (pintype "passive"))
      (node (ref "C22") (pin "2") (pinfunction "2_2") (pintype "passive"))
      (node (ref "C23") (pin "2") (pinfunction "2_2") (pintype "passive"))
      (node (ref "C3") (pin "2") (pinfunction "2_2") (pintype "passive"))
      (node (ref "C30") (pin "1") (pinfunction "1_1") (pintype "passive"))
      (node (ref "C31") (pin "1") (pinfunction "1_1") (pintype "passive"))
      (node (ref "C34") (pin "1") (pinfunction "1_1") (pintype "passive"))
      (node (ref "C35") (pin "1") (pinfunction "1_1") (pintype "passive"))
      (node (ref "C36") (pin "1") (pinfunction "1_1") (pintype "passive"))
      (node (ref "C37") (pin "1") (pinfunction "1_1") (pintype "passive"))
      (node (ref "C38") (pin "2") (pinfunction "2_2") (pintype "passive"))
      (node (ref "C39") (pin "2") (pinfunction "2_2") (pintype "passive"))
      (node (ref "C40") (pin "2") (pinfunction "2_2") (pintype "passive"))
      (node (ref "C7") (pin "1") (pinfunction "1_1") (pintype "passive"))
      (node (ref "R15") (pin "2") (pinfunction "2_2") (pintype "passive"))
      (node (ref "R16") (pin "2") (pinfunction "2_2") (pintype "passive"))
      (node (ref "R5") (pin "1") (pinfunction "1_1") (pintype "passive"))
      (node (ref "RN8") (pin "3") (pinfunction "1_3") (pintype "passive"))
      (node (ref "RN8") (pin "4") (pinfunction "1_4") (pintype "passive"))
      (node (ref "U1") (pin "18") (pinfunction "VCC_IO1_18") (pintype "power_in"))
      (node (ref "U1") (pin "31") (pinfunction "VCC_IO4_31") (pintype "power_in"))
      (node (ref "U1") (pin "46") (pinfunction "VCC_IO4_46") (pintype "power_in"))
      (node (ref "U1") (pin "59") (pinfunction "VCC_IO3_59") (pintype "power_in"))
      (node (ref "U1") (pin "80") (pinfunction "VCC_IO2_80") (pintype "power_in"))
      (node (ref "U1") (pin "95") (pinfunction "VCC_IO2_95") (pintype "power_in"))
      (node (ref "U2") (pin "1") (pinfunction "VCCA_1") (pintype "power_in"))
      (node (ref "U4") (pin "23") (pinfunction "VCCB_23") (pintype "power_in"))
      (node (ref "U4") (pin "24") (pinfunction "VCCB_24") (pintype "power_in"))
      (node (ref "U5") (pin "5") (pinfunction "VCC_5") (pintype "power_in"))
      (node (ref "U7") (pin "3") (pinfunction "VCC_3") (pintype "power_in"))
      (node (ref "U7") (pin "7") (pinfunction "VCC_7") (pintype "power_in"))
      (node (ref "U7") (pin "8") (pinfunction "VCC_8") (pintype "power_in"))
      (node (ref "U8") (pin "5") (pinfunction "VCC_5") (pintype "power_in"))
      (node (ref "VR3") (pin "2") (pinfunction "VOUT_2") (pintype "power_in"))
      (node (ref "VR4") (pin "3") (pinfunction "VIN_3") (pintype "power_in"))
      (node (ref "X1") (pin "4") (pinfunction "S_4") (pintype "passive"))
      (node (ref "XO1") (pin "4") (pinfunction "VDD_4") (pintype "power_in"))
      (node (ref "XO2") (pin "4") (pinfunction "VDD_4") (pintype "power_in"))
    )
    (net (code "183") (name "unconnected-(U1-{slash}CEO-Pad12)") (class "Default")
      (node (ref "U1") (pin "12") (pinfunction "/CEO_12") (pintype "output"))
    )
    (net (code "184") (name "unconnected-(U9-CH1_OUT-Pad8)") (class "Default")
      (node (ref "U9") (pin "8") (pinfunction "CH1_OUT_8") (pintype "output"))
    )
    (net (code "185") (name "unconnected-(U9-CH2_OUT-Pad7)") (class "Default")
      (node (ref "U9") (pin "7") (pinfunction "CH2_OUT_7") (pintype "output"))
    )
    (net (code "186") (name "unconnected-(X1G-S-Pad6)") (class "Default")
      (node (ref "X1") (pin "6") (pinfunction "S_6") (pintype "passive"))
    )
    (net (code "187") (name "unconnected-(X1H-S-Pad7)") (class "Default")
      (node (ref "X1") (pin "7") (pinfunction "S_7") (pintype "passive"))
    )
    (net (code "188") (name "unconnected-(X1I-S-Pad8)") (class "Default")
      (node (ref "X1") (pin "8") (pinfunction "S_8") (pintype "passive"))
    )
    (net (code "189") (name "unconnected-(X2B-F-Pad10)") (class "Default")
      (node (ref "X2") (pin "10") (pinfunction "F_10") (pintype "passive"))
    )
    (net (code "190") (name "unconnected-(X2C-F-Pad11)") (class "Default")
      (node (ref "X2") (pin "11") (pinfunction "F_11") (pintype "passive"))
    )
    (net (code "191") (name "unconnected-(X2E-F-Pad13)") (class "Default")
      (node (ref "X2") (pin "13") (pinfunction "F_13") (pintype "passive"))
    )
    (net (code "192") (name "unconnected-(X2F-F-Pad14)") (class "Default")
      (node (ref "X2") (pin "14") (pinfunction "F_14") (pintype "passive"))
    )
    (net (code "193") (name "unconnected-(X2H-F-Pad2)") (class "Default")
      (node (ref "X2") (pin "2") (pinfunction "F_2") (pintype "passive"))
    )
    (net (code "194") (name "unconnected-(X2I-F-Pad3)") (class "Default")
      (node (ref "X2") (pin "3") (pinfunction "F_3") (pintype "passive"))
    )
    (net (code "195") (name "unconnected-(X2J-F-Pad4)") (class "Default")
      (node (ref "X2") (pin "4") (pinfunction "F_4") (pintype "passive"))
    )
    (net (code "196") (name "unconnected-(X2K-F-Pad5)") (class "Default")
      (node (ref "X2") (pin "5") (pinfunction "F_5") (pintype "passive"))
    )
    (net (code "197") (name "unconnected-(X2L-F-Pad6)") (class "Default")
      (node (ref "X2") (pin "6") (pinfunction "F_6") (pintype "passive"))
    )
    (net (code "198") (name "unconnected-(X2M-F-Pad7)") (class "Default")
      (node (ref "X2") (pin "7") (pinfunction "F_7") (pintype "passive"))
    )
    (net (code "199") (name "unconnected-(X4B-F-Pad10)") (class "Default")
      (node (ref "X4") (pin "10") (pinfunction "F_10") (pintype "passive"))
    )
    (net (code "200") (name "unconnected-(X4C-F-Pad11)") (class "Default")
      (node (ref "X4") (pin "11") (pinfunction "F_11") (pintype "passive"))
    )
    (net (code "201") (name "unconnected-(X4E-F-Pad13)") (class "Default")
      (node (ref "X4") (pin "13") (pinfunction "F_13") (pintype "passive"))
    )
    (net (code "202") (name "unconnected-(X4F-F-Pad14)") (class "Default")
      (node (ref "X4") (pin "14") (pinfunction "F_14") (pintype "passive"))
    )
    (net (code "203") (name "unconnected-(X4H-F-Pad2)") (class "Default")
      (node (ref "X4") (pin "2") (pinfunction "F_2") (pintype "passive"))
    )
    (net (code "204") (name "unconnected-(X4I-F-Pad3)") (class "Default")
      (node (ref "X4") (pin "3") (pinfunction "F_3") (pintype "passive"))
    )
    (net (code "205") (name "unconnected-(X4J-F-Pad4)") (class "Default")
      (node (ref "X4") (pin "4") (pinfunction "F_4") (pintype "passive"))
    )
    (net (code "206") (name "unconnected-(X4K-F-Pad5)") (class "Default")
      (node (ref "X4") (pin "5") (pinfunction "F_5") (pintype "passive"))
    )
    (net (code "207") (name "unconnected-(X4L-F-Pad6)") (class "Default")
      (node (ref "X4") (pin "6") (pinfunction "F_6") (pintype "passive"))
    )
    (net (code "208") (name "unconnected-(X4M-F-Pad7)") (class "Default")
      (node (ref "X4") (pin "7") (pinfunction "F_7") (pintype "passive"))
    )
    (net (code "209") (name "unconnected-(XO1-TS-Pad1)") (class "Default")
      (node (ref "XO1") (pin "1") (pinfunction "TS_1") (pintype "passive"))
    )
    (net (code "210") (name "unconnected-(XO2-TS-Pad1)") (class "Default")
      (node (ref "XO2") (pin "1") (pinfunction "TS_1") (pintype "passive"))
    )
  )
)
